# Control_Sense_TOP_VAC.net
KiCad netlist of a schematic drawn in Altium Designer
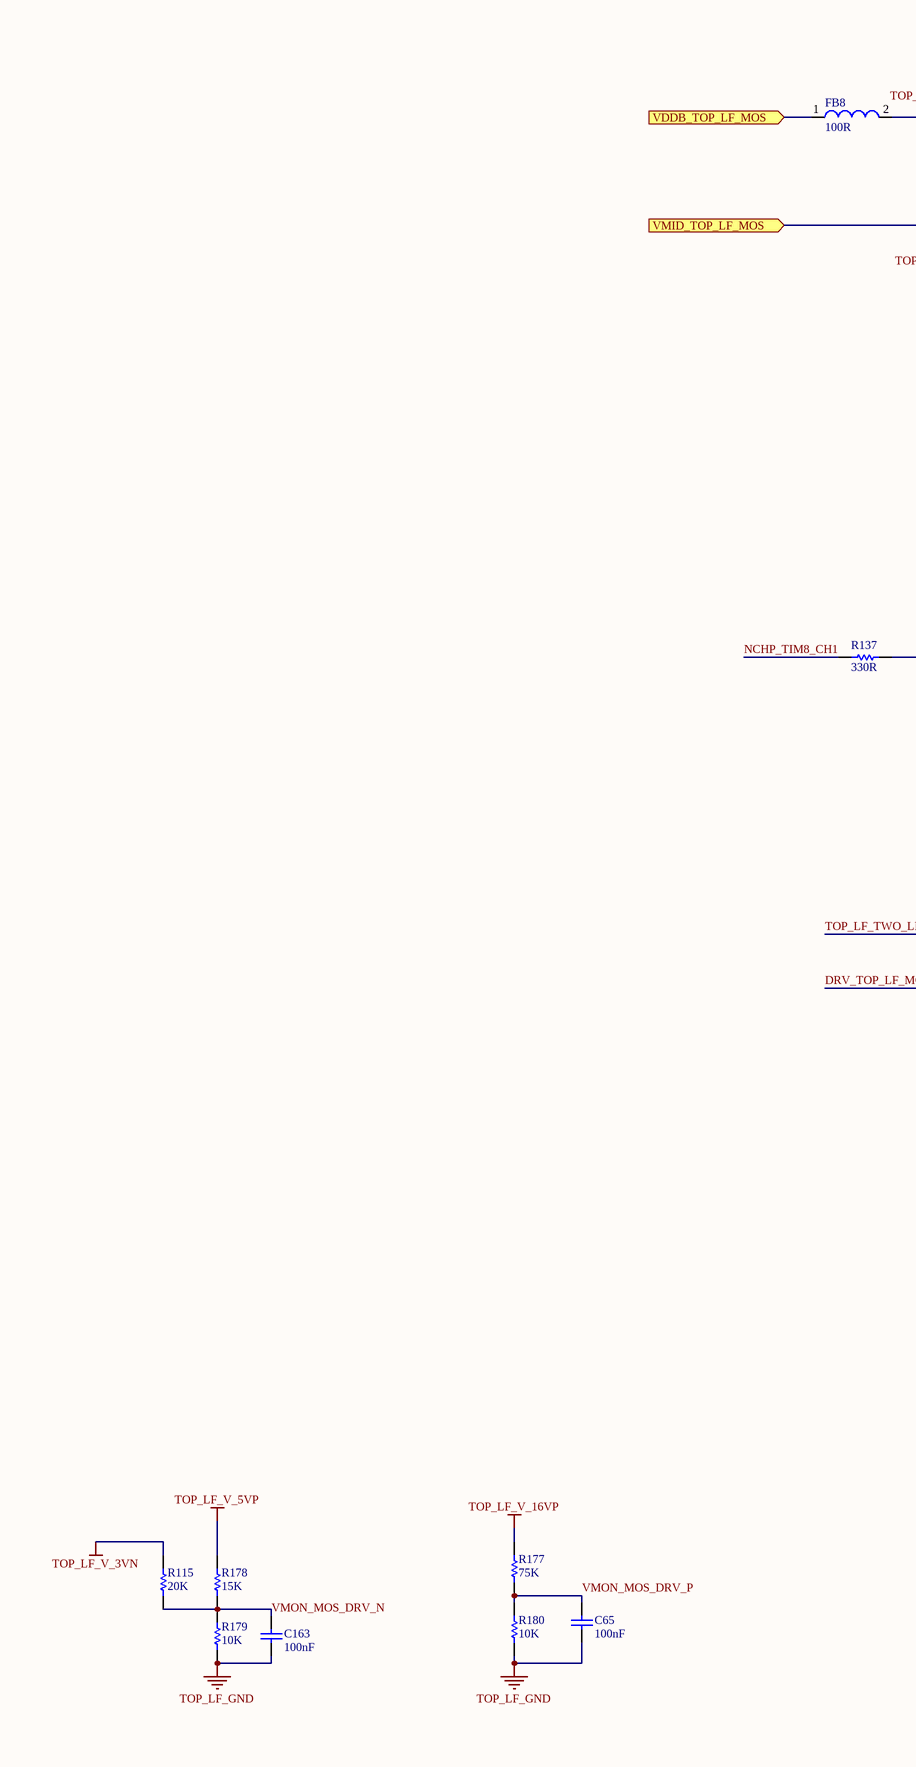
[diagram p0: Control_Sense_TOP_VAC.SchDoc, top left]
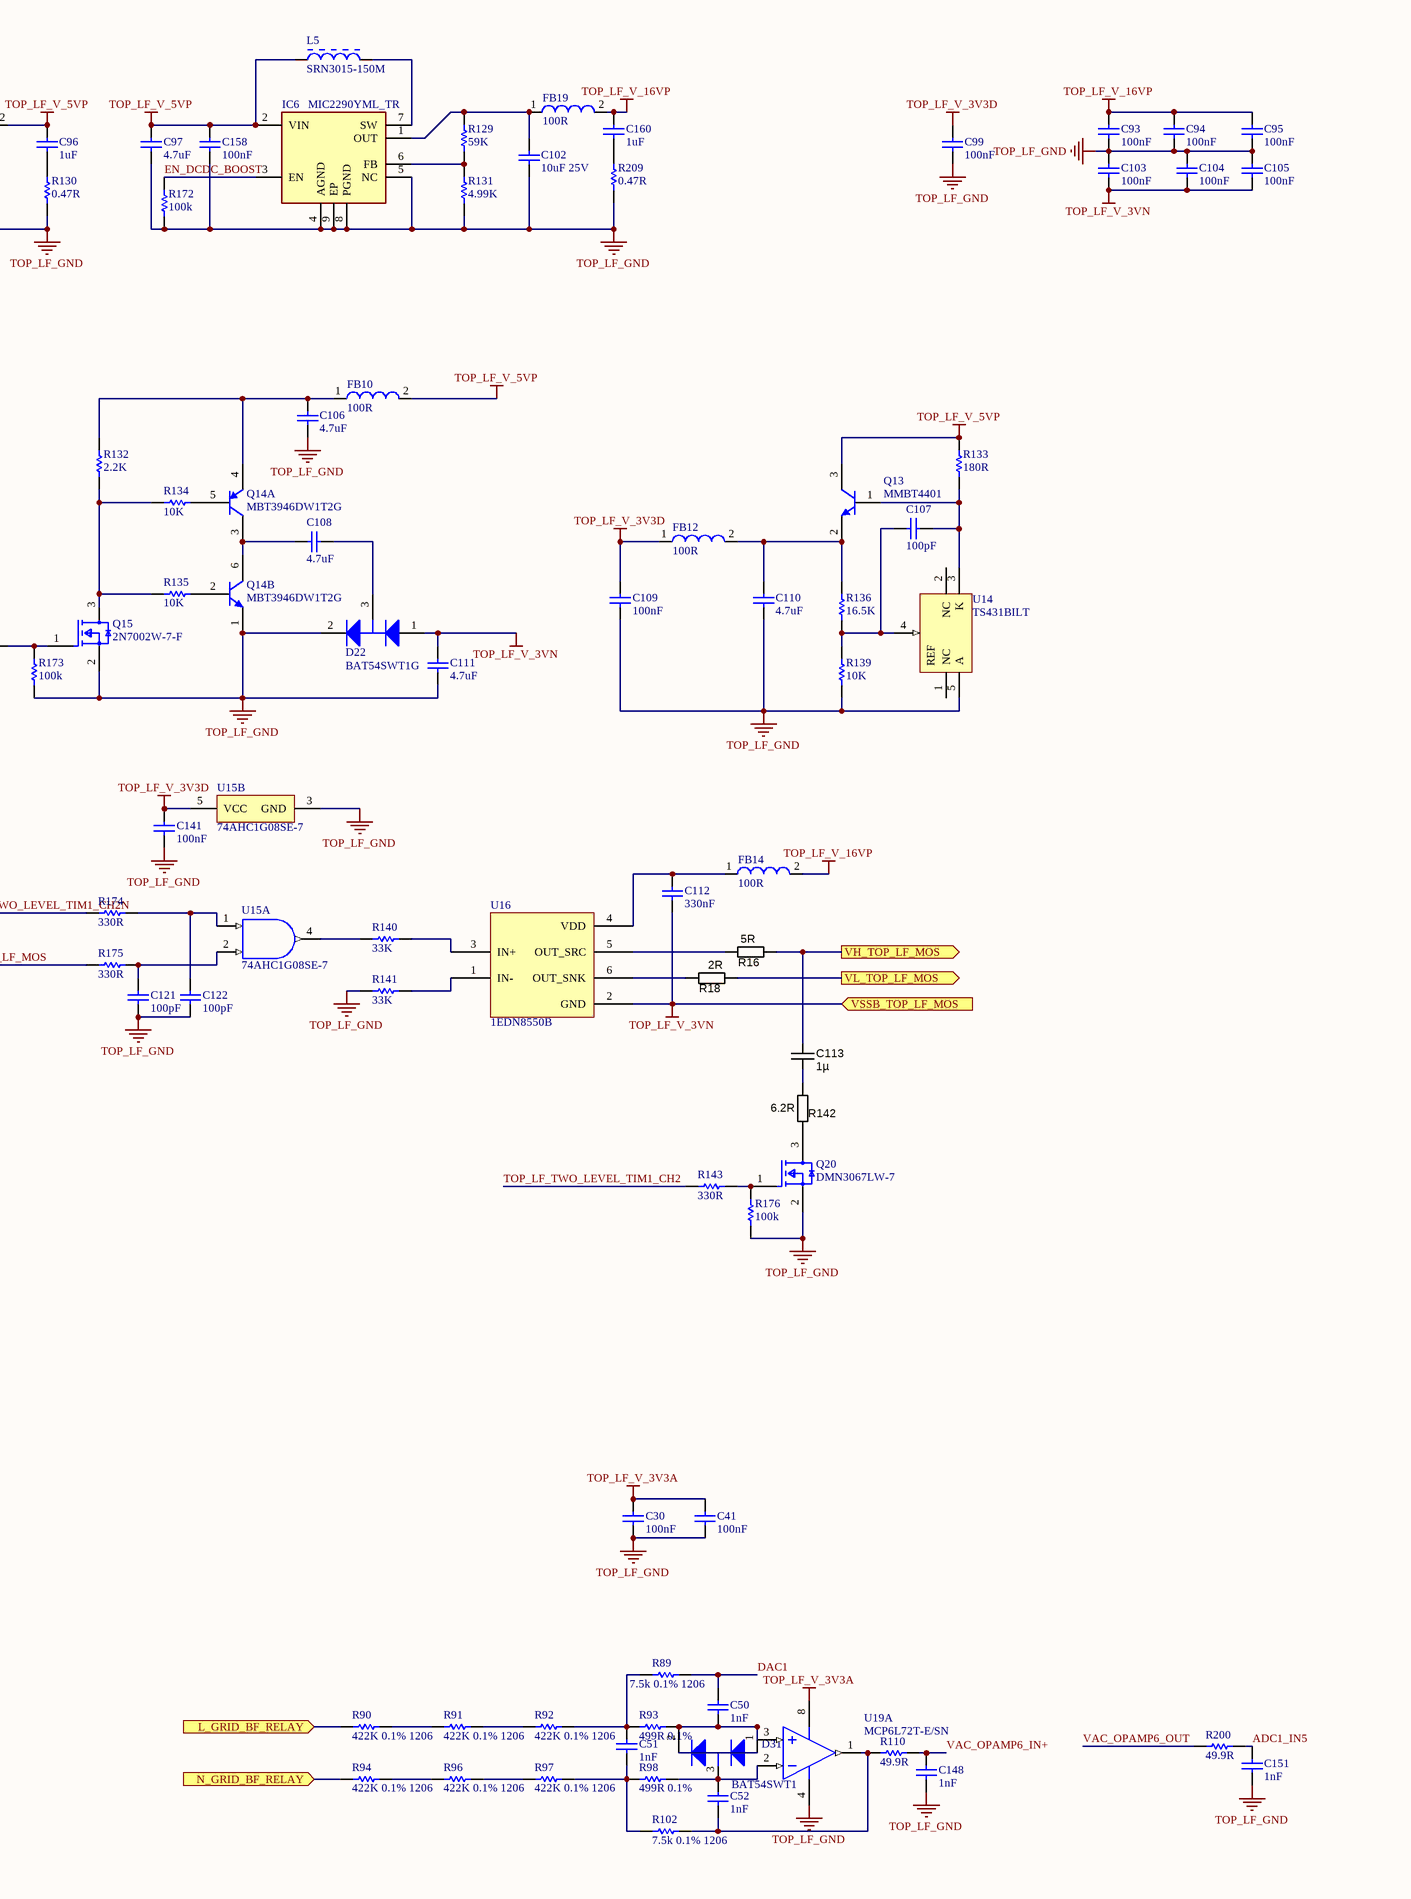
[diagram p1: Control_Sense_TOP_VAC.SchDoc, top right]
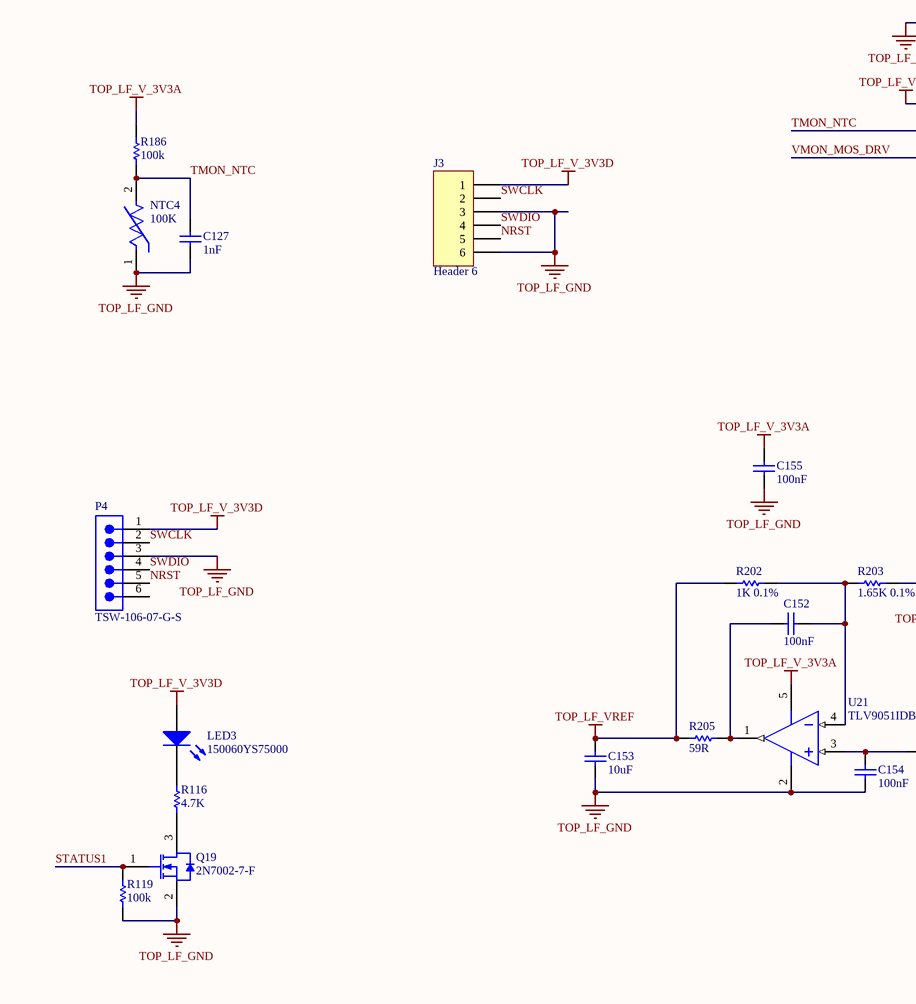
[diagram p2: Control_Sense_TOP_VAC.SchDoc, bottom left]
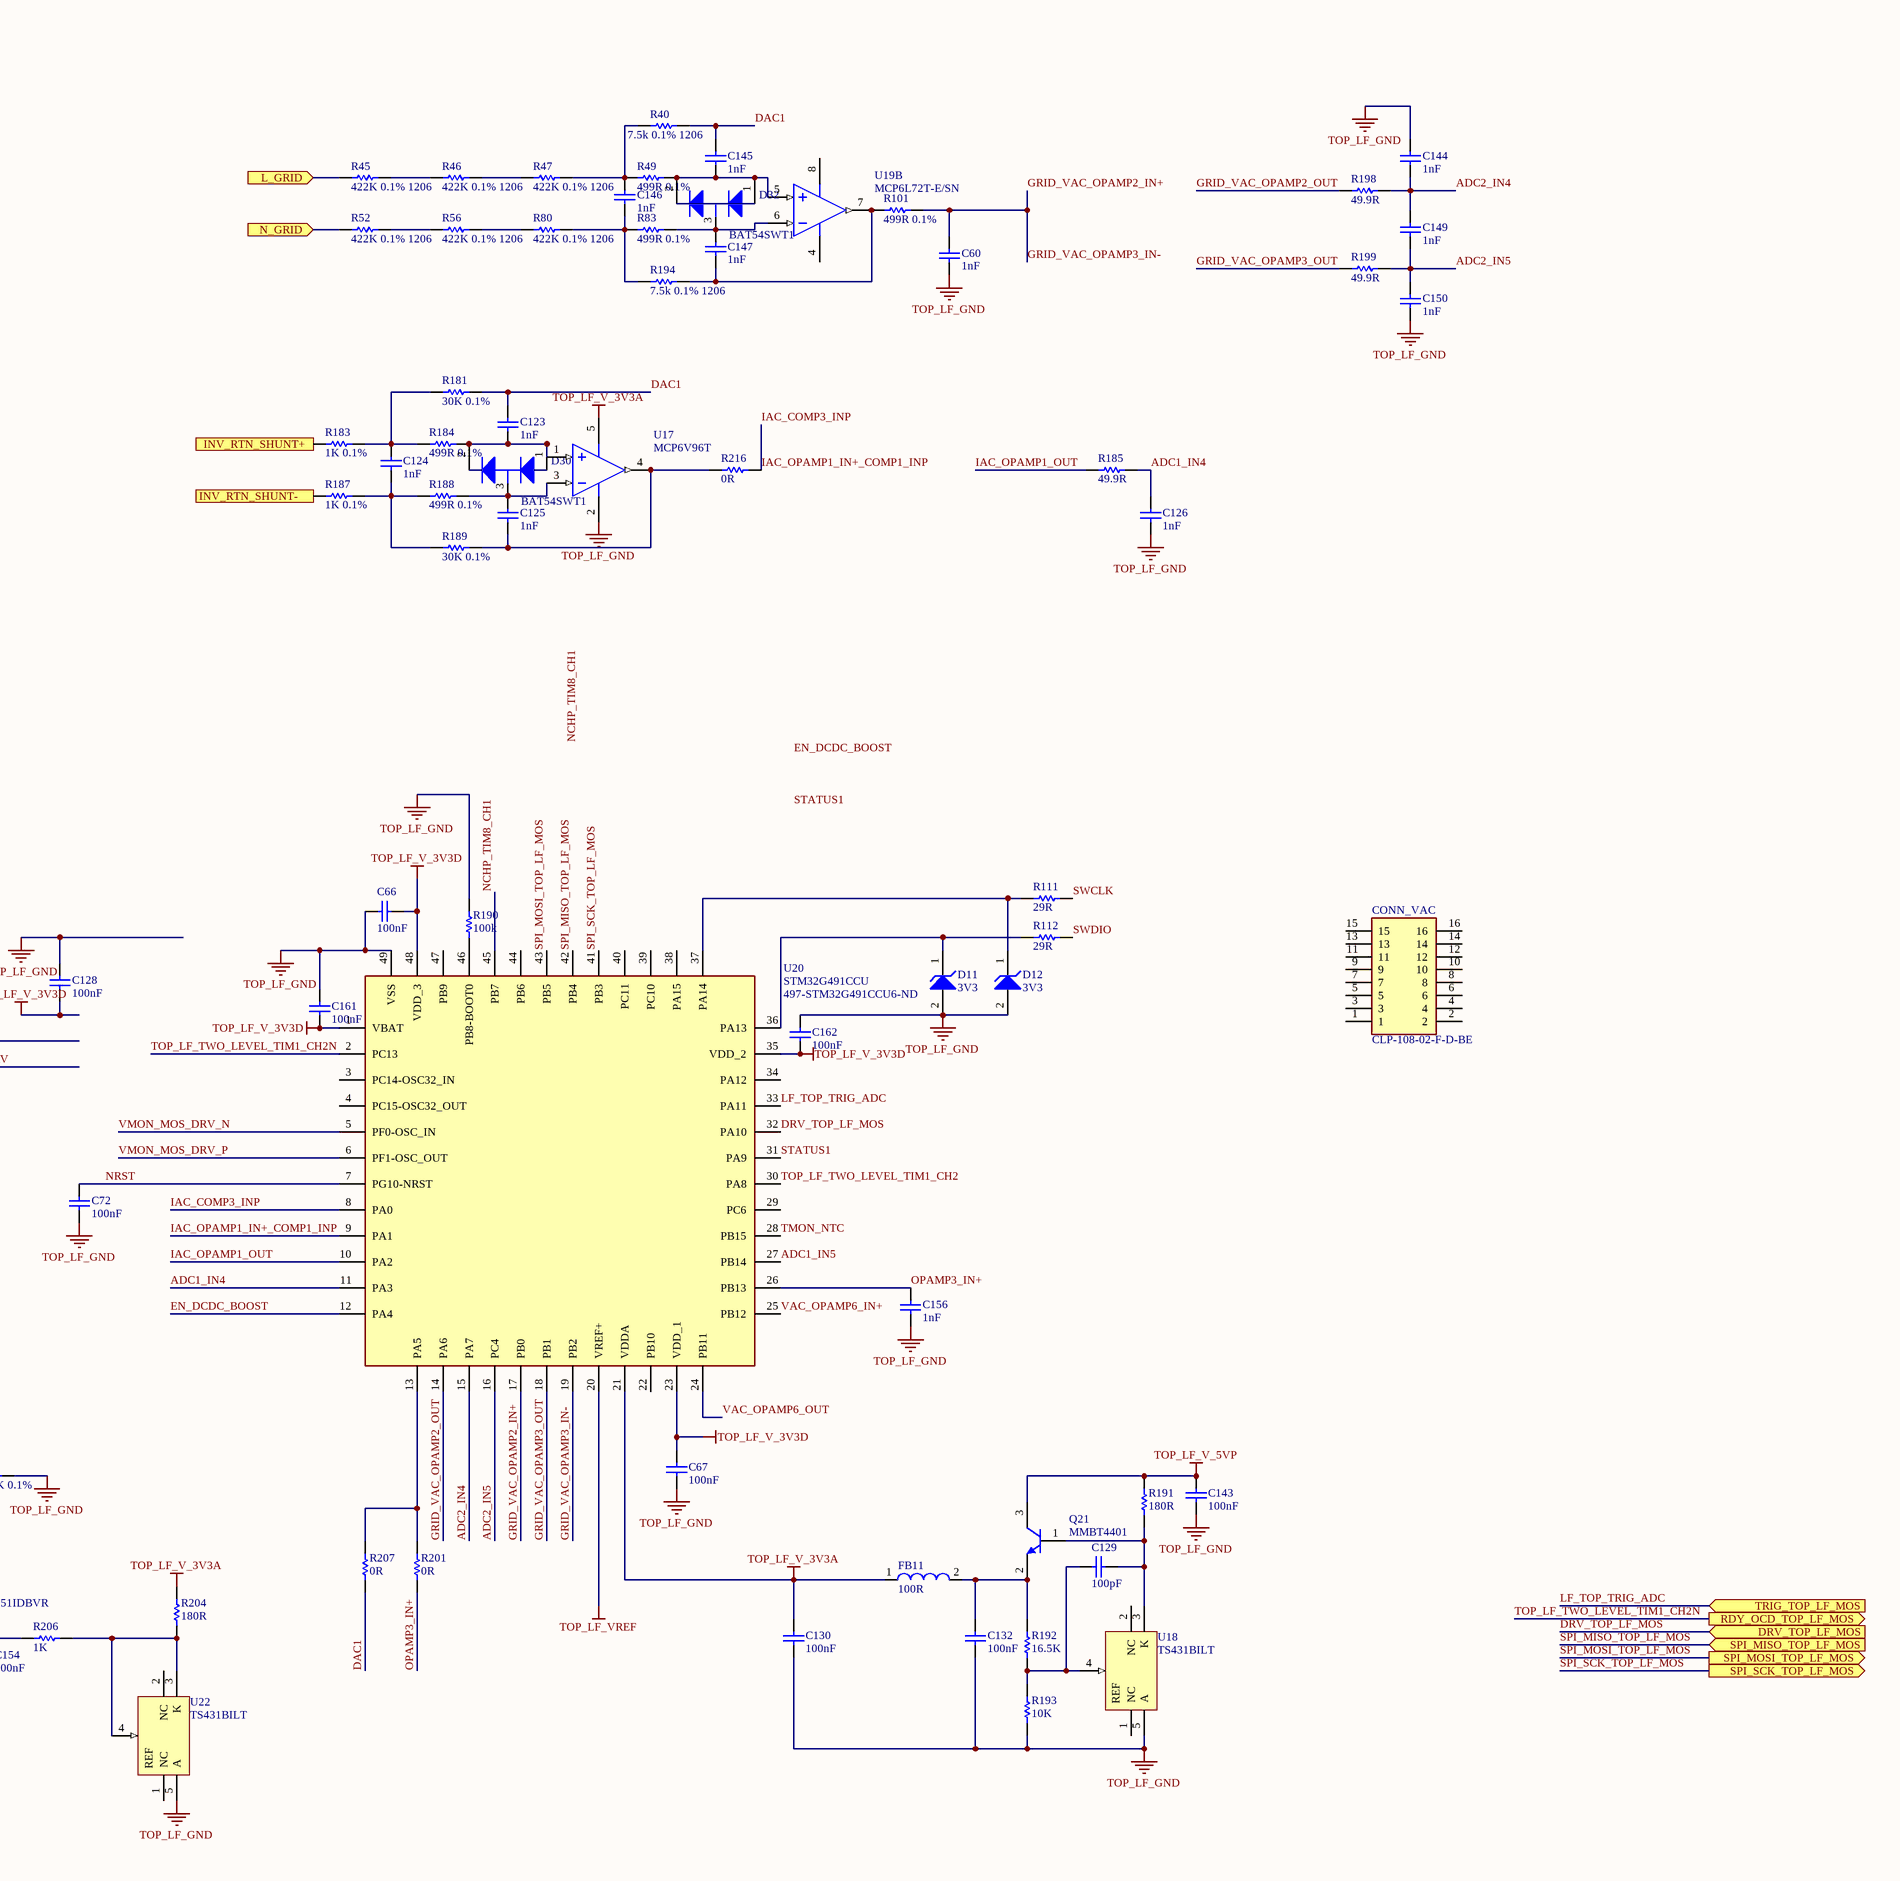
[diagram p3: Control_Sense_TOP_VAC.SchDoc, bottom right]

(export (version "E")
  (design (tool "Eeschema 10.0.6"))
  (components
    (comp (ref "C30")
      (value "100nF")
      (footprint "SAMS-C0603-2_N")
      (description "Cap Ceramic 0.1uF 50VDC X7R 10% SMD 0603 Paper T/R")
      (fields
        (field (name "MANUFACTURER") "Samsung Electro-Mechanics")
        (field (name "MANUFACTURER PART NUMBER") "CL10B104KB8NNNC")
      )
      (libsource (lib "Altium Content Vault") (part "CAP-NP-2"))
    )
    (comp (ref "C41")
      (value "100nF")
      (footprint "SAMS-C0603-2_N")
      (description "Cap Ceramic 0.1uF 50VDC X7R 10% SMD 0603 Paper T/R")
      (fields
        (field (name "MANUFACTURER") "Samsung Electro-Mechanics")
        (field (name "MANUFACTURER PART NUMBER") "CL10B104KB8NNNC")
      )
      (libsource (lib "Altium Content Vault") (part "CAP-NP-2"))
    )
    (comp (ref "C50")
      (value "1nF")
      (footprint "CAPC1608X90X35NL15T15")
      (fields
        (field (name "MANUFACTURER") "AVX Interconnect / Elco")
        (field (name "PART NUMBER") "06035A151JAT2A.")
        (field (name "MANUFACTURER PART NUMBER") "06035A151JAT2A")
      )
      (libsource (lib "Altium Content Vault") (part "CAP"))
    )
    (comp (ref "C51")
      (value "1nF")
      (footprint "CAPC1608X90X35NL15T15")
      (fields
        (field (name "MANUFACTURER") "AVX Interconnect / Elco")
        (field (name "PART NUMBER") "06035A151JAT2A.")
        (field (name "MANUFACTURER PART NUMBER") "06035A151JAT2A")
      )
      (libsource (lib "Altium Content Vault") (part "CAP"))
    )
    (comp (ref "C52")
      (value "1nF")
      (footprint "CAPC1608X90X35NL15T15")
      (fields
        (field (name "MANUFACTURER") "AVX Interconnect / Elco")
        (field (name "PART NUMBER") "06035A151JAT2A.")
        (field (name "MANUFACTURER PART NUMBER") "06035A151JAT2A")
      )
      (libsource (lib "Altium Content Vault") (part "CAP"))
    )
    (comp (ref "C60")
      (value "1nF")
      (footprint "CAPC1608X90X35LL15T15")
      (fields
        (field (name "MANUFACTURER") "AVX Interconnect / Elco")
        (field (name "PART NUMBER") "06035A151JAT2A.")
        (field (name "MANUFACTURER PART NUMBER") "06035A151JAT2A")
      )
      (libsource (lib "Altium Content Vault") (part "CAP"))
    )
    (comp (ref "C65")
      (value "100nF")
      (footprint "CAPC1005X56X25NL10T15")
      (fields
        (field (name "MANUFACTURER") "AVX Interconnect / Elco")
        (field (name "PART NUMBER") "04026D104KAT2A")
        (field (name "TOLERANCE") "10%")
      )
      (libsource (lib "Altium Content Vault") (part "CAP"))
    )
    (comp (ref "C66")
      (value "100nF")
      (footprint "SAMS-C0603-2_L")
      (description "Cap Ceramic 0.1uF 50VDC X7R 10% SMD 0603 Paper T/R")
      (fields
        (field (name "MANUFACTURER") "Samsung Electro-Mechanics")
        (field (name "MANUFACTURER PART NUMBER") "CL10B104KB8NNNC")
      )
      (libsource (lib "Altium Content Vault") (part "CAP-NP-2"))
    )
    (comp (ref "C67")
      (value "100nF")
      (footprint "SAMS-C0603-2_L")
      (description "Cap Ceramic 0.1uF 50VDC X7R 10% SMD 0603 Paper T/R")
      (fields
        (field (name "MANUFACTURER") "Samsung Electro-Mechanics")
        (field (name "MANUFACTURER PART NUMBER") "CL10B104KB8NNNC")
      )
      (libsource (lib "Altium Content Vault") (part "CAP-NP-2"))
    )
    (comp (ref "C72")
      (value "100nF")
      (footprint "CAPC1005X56X25NL10T15")
      (fields
        (field (name "MANUFACTURER") "AVX Interconnect / Elco")
        (field (name "PART NUMBER") "04026D104KAT2A")
        (field (name "TOLERANCE") "10%")
      )
      (libsource (lib "Altium Content Vault") (part "CAP"))
    )
    (comp (ref "C93")
      (value "100nF")
      (footprint "CAPC1608X90X35NL15T15")
      (fields
        (field (name "MANUFACTURER") "AVX Interconnect / Elco")
        (field (name "PART NUMBER") "06035A151JAT2A.")
        (field (name "MANUFACTURER PART NUMBER") "06035A151JAT2A")
      )
      (libsource (lib "Altium Content Vault") (part "CAP"))
    )
    (comp (ref "C94")
      (value "100nF")
      (footprint "CAPC1608X90X35NL15T15")
      (fields
        (field (name "MANUFACTURER") "AVX Interconnect / Elco")
        (field (name "PART NUMBER") "06035A151JAT2A.")
        (field (name "MANUFACTURER PART NUMBER") "06035A151JAT2A")
      )
      (libsource (lib "Altium Content Vault") (part "CAP"))
    )
    (comp (ref "C95")
      (value "100nF")
      (footprint "CAPC1608X90X35NL15T15")
      (fields
        (field (name "MANUFACTURER") "AVX Interconnect / Elco")
        (field (name "PART NUMBER") "06035A151JAT2A.")
        (field (name "MANUFACTURER PART NUMBER") "06035A151JAT2A")
      )
      (libsource (lib "Altium Content Vault") (part "CAP"))
    )
    (comp (ref "C96")
      (value "1uF")
      (footprint "CAPC2013X140X50LL20T25")
      (description "SMD Multilayer Ceramic Capacitor, 1 µF, 25 V, 0805 [2012 Metric], ± 10%, X7R")
      (fields (field (name "PART NUMBER") "C0805C105K3RACTU") (field (name "MANUFACTURER") "Kemet"))
      (libsource (lib "Altium Content Vault") (part "CAP"))
    )
    (comp (ref "C97")
      (value "4.7uF")
      (footprint "CAPC2013X145X20NL20")
      (description "Chip Capacitor, 4.7 uF, +/- 10%, 25 V, -55 to 125 degC, 0805 (2012 Metric), RoHS, Tape and Reel")
      (fields (field (name "MANUFACTURER") "TDK") (field (name "TOLERANCE") "±10%"))
      (libsource (lib "Altium Content Vault") (part "CAP-NP-2"))
    )
    (comp (ref "C99")
      (value "100nF")
      (footprint "CAPC1608X90X35ML15T15")
      (fields
        (field (name "MANUFACTURER") "AVX Interconnect / Elco")
        (field (name "PART NUMBER") "06035A151JAT2A.")
        (field (name "MANUFACTURER PART NUMBER") "06035A151JAT2A")
      )
      (libsource (lib "Altium Content Vault") (part "CAP"))
    )
    (comp (ref "C102")
      (value "10uF 25V")
      (footprint "CAPC3216X229X50LL20T25")
      (description "Chip Capacitor, 10 uF, +/- 10%, 25 V, -55 to 85 degC, 1206 (3216 Metric), RoHS, Tape and Reel")
      (fields (field (name "MANUFACTURER") "AVX"))
      (libsource (lib "Altium Content Vault") (part "CAP-NP-2"))
    )
    (comp (ref "C103")
      (value "100nF")
      (footprint "CAPC1608X90X35NL15T15")
      (fields
        (field (name "MANUFACTURER") "AVX Interconnect / Elco")
        (field (name "PART NUMBER") "06035A151JAT2A.")
        (field (name "MANUFACTURER PART NUMBER") "06035A151JAT2A")
      )
      (libsource (lib "Altium Content Vault") (part "CAP"))
    )
    (comp (ref "C104")
      (value "100nF")
      (footprint "CAPC1608X90X35NL15T15")
      (fields
        (field (name "MANUFACTURER") "AVX Interconnect / Elco")
        (field (name "PART NUMBER") "06035A151JAT2A.")
        (field (name "MANUFACTURER PART NUMBER") "06035A151JAT2A")
      )
      (libsource (lib "Altium Content Vault") (part "CAP"))
    )
    (comp (ref "C105")
      (value "100nF")
      (footprint "CAPC1608X90X35NL15T15")
      (fields
        (field (name "MANUFACTURER") "AVX Interconnect / Elco")
        (field (name "PART NUMBER") "06035A151JAT2A.")
        (field (name "MANUFACTURER PART NUMBER") "06035A151JAT2A")
      )
      (libsource (lib "Altium Content Vault") (part "CAP"))
    )
    (comp (ref "C106")
      (value "4.7uF")
      (footprint "SAMS-C0603-2_L")
      (description "Cap Ceramic 0.1uF 50VDC X7R 10% SMD 0603 Paper T/R")
      (fields
        (field (name "MANUFACTURER") "Samsung Electro-Mechanics")
        (field (name "MANUFACTURER PART NUMBER") "CL10B104KB8NNNC")
      )
      (libsource (lib "Altium Content Vault") (part "CAP-NP-2"))
    )
    (comp (ref "C107")
      (value "100pF")
      (footprint "CAPC1608X90X35NL10T15")
      (description "0603 100pF 50V ±5 % Tolerance C0G SMT Multilayer Ceramic Capacitor")
      (fields (field (name "PART NUMBER") "GRM1885C1H101JA01D") (field (name "MANUFACTURER") "Murata"))
      (libsource (lib "Altium Content Vault") (part "CAP"))
    )
    (comp (ref "C108")
      (value "4.7uF")
      (footprint "SAMS-C0603-2_L")
      (description "Cap Ceramic 0.1uF 50VDC X7R 10% SMD 0603 Paper T/R")
      (fields
        (field (name "MANUFACTURER") "Samsung Electro-Mechanics")
        (field (name "MANUFACTURER PART NUMBER") "CL10B104KB8NNNC")
      )
      (libsource (lib "Altium Content Vault") (part "CAP-NP-2"))
    )
    (comp (ref "C109")
      (value "100nF")
      (footprint "SAMS-C0603-2_N")
      (description "Cap Ceramic 0.1uF 50VDC X7R 10% SMD 0603 Paper T/R")
      (fields
        (field (name "MANUFACTURER") "Samsung Electro-Mechanics")
        (field (name "MANUFACTURER PART NUMBER") "CL10B104KB8NNNC")
      )
      (libsource (lib "Altium Content Vault") (part "CAP-NP-2"))
    )
    (comp (ref "C110")
      (value "4.7uF")
      (footprint "CAPC1608X90X35LL15T15")
      (description "Cap Ceramic 4.7uF 6.3VDC X5R 10% SMD 0603 Paper T/R")
      (fields
        (field (name "PART NUMBER") "06036D475KAT2A")
        (field (name "MANUFACTURER") "AVX Interconnect / Elco")
      )
      (libsource (lib "Altium Content Vault") (part "CAP"))
    )
    (comp (ref "C111")
      (value "4.7uF")
      (footprint "SAMS-C0603-2_L")
      (description "Cap Ceramic 4.7uF 6.3VDC X5R 10% SMD 0603 Paper T/R")
      (fields
        (field (name "MANUFACTURER") "Samsung Electro-Mechanics")
        (field (name "MANUFACTURER PART NUMBER") "CL10B104KB8NNNC")
      )
      (libsource (lib "Altium Content Vault") (part "CAP-NP-2"))
    )
    (comp (ref "C112")
      (value "330nF")
      (footprint "CAPC2013X135X45NL10T25")
      (description "Chip Capacitor, 0.1 uF, +/- 10%, 50 V, -55 to 125 degC, 0805 (2012 Metric), RoHS, Tape and Reel")
      (fields (field (name "VOLTAGE") "50V") (field (name "TOLERANCE") "10%"))
      (libsource (lib "Altium Content Vault") (part "CAP-NP-2"))
    )
    (comp (ref "C113")
      (value "1µ")
      (footprint "CAPC2012X135N")
      (description "Capacitor SMD Cer 1uF 10% 16V X7R 0805")
      (fields (field (name "TOLERANCE") "±10%") (field (name "Comment") "approved sub OK"))
      (libsource (lib "PBL - Capacitors") (part "CAPC_1u_0805_X7R_16V_10%"))
    )
    (comp (ref "C121")
      (value "100pF")
      (footprint "CAPC1608X90X35NL10T15")
      (fields
        (field (name "PART NUMBER") "GRM1885C1H101JA01D")
        (field (name "MANUFACTURER") "Murata")
        (field (name "TOLERANCE") "5%")
      )
      (libsource (lib "Altium Content Vault") (part "CAP"))
    )
    (comp (ref "C122")
      (value "100pF")
      (footprint "CAPC1608X90X35NL10T15")
      (fields
        (field (name "PART NUMBER") "GRM1885C1H101JA01D")
        (field (name "MANUFACTURER") "Murata")
        (field (name "TOLERANCE") "5%")
      )
      (libsource (lib "Altium Content Vault") (part "CAP"))
    )
    (comp (ref "C123")
      (value "1nF")
      (footprint "CAPC1608X90X35NL15T15")
      (fields
        (field (name "MANUFACTURER") "AVX Interconnect / Elco")
        (field (name "PART NUMBER") "06035A151JAT2A.")
        (field (name "MANUFACTURER PART NUMBER") "06035A151JAT2A")
      )
      (libsource (lib "Altium Content Vault") (part "CAP"))
    )
    (comp (ref "C124")
      (value "1nF")
      (footprint "CAPC1608X90X35LL15T15")
      (fields
        (field (name "MANUFACTURER") "AVX Interconnect / Elco")
        (field (name "PART NUMBER") "06035A151JAT2A.")
        (field (name "MANUFACTURER PART NUMBER") "06035A151JAT2A")
      )
      (libsource (lib "Altium Content Vault") (part "CAP"))
    )
    (comp (ref "C125")
      (value "1nF")
      (footprint "CAPC1608X90X35NL15T15")
      (fields
        (field (name "MANUFACTURER") "AVX Interconnect / Elco")
        (field (name "PART NUMBER") "06035A151JAT2A.")
        (field (name "MANUFACTURER PART NUMBER") "06035A151JAT2A")
      )
      (libsource (lib "Altium Content Vault") (part "CAP"))
    )
    (comp (ref "C126")
      (value "1nF")
      (footprint "CAPC1005X56X25NL10T15")
      (fields
        (field (name "MANUFACTURER") "AVX Interconnect / Elco")
        (field (name "PART NUMBER") "04025C102MAT2A")
        (field (name "TOLERANCE") "20%")
      )
      (libsource (lib "Altium Content Vault") (part "CAP"))
    )
    (comp (ref "C127")
      (value "1nF")
      (footprint "CAPC1005X56X25NL10T15")
      (fields
        (field (name "MANUFACTURER") "AVX Interconnect / Elco")
        (field (name "PART NUMBER") "04025C102MAT2A")
        (field (name "TOLERANCE") "20%")
      )
      (libsource (lib "Altium Content Vault") (part "CAP"))
    )
    (comp (ref "C128")
      (value "100nF")
      (footprint "SAMS-C0603-2_N")
      (description "Cap Ceramic 0.1uF 50VDC X7R 10% SMD 0603 Paper T/R")
      (fields
        (field (name "MANUFACTURER") "Samsung Electro-Mechanics")
        (field (name "MANUFACTURER PART NUMBER") "CL10B104KB8NNNC")
      )
      (libsource (lib "Altium Content Vault") (part "CAP-NP-2"))
    )
    (comp (ref "C129")
      (value "100pF")
      (footprint "CAPC1608X90X35NL10T15")
      (description "0603 100pF 50V ±5 % Tolerance C0G SMT Multilayer Ceramic Capacitor")
      (fields (field (name "PART NUMBER") "GRM1885C1H101JA01D") (field (name "MANUFACTURER") "Murata"))
      (libsource (lib "Altium Content Vault") (part "CAP"))
    )
    (comp (ref "C130")
      (value "100nF")
      (footprint "SAMS-C0603-2_L")
      (description "Cap Ceramic 0.1uF 50VDC X7R 10% SMD 0603 Paper T/R")
      (fields
        (field (name "MANUFACTURER") "Samsung Electro-Mechanics")
        (field (name "MANUFACTURER PART NUMBER") "CL10B104KB8NNNC")
      )
      (libsource (lib "Altium Content Vault") (part "CAP-NP-2"))
    )
    (comp (ref "C132")
      (value "100nF")
      (footprint "SAMS-C0603-2_N")
      (description "Cap Ceramic 0.1uF 50VDC X7R 10% SMD 0603 Paper T/R")
      (fields
        (field (name "MANUFACTURER") "Samsung Electro-Mechanics")
        (field (name "MANUFACTURER PART NUMBER") "CL10B104KB8NNNC")
      )
      (libsource (lib "Altium Content Vault") (part "CAP-NP-2"))
    )
    (comp (ref "C141")
      (value "100nF")
      (footprint "CAPC1608X90X35LL15T15")
      (fields
        (field (name "MANUFACTURER") "AVX Interconnect / Elco")
        (field (name "PART NUMBER") "06035A151JAT2A.")
        (field (name "MANUFACTURER PART NUMBER") "06035A151JAT2A")
      )
      (libsource (lib "Altium Content Vault") (part "CAP"))
    )
    (comp (ref "C143")
      (value "100nF")
      (footprint "SAMS-C0603-2_N")
      (description "Cap Ceramic 0.1uF 50VDC X7R 10% SMD 0603 Paper T/R")
      (fields
        (field (name "MANUFACTURER") "Samsung Electro-Mechanics")
        (field (name "MANUFACTURER PART NUMBER") "CL10B104KB8NNNC")
      )
      (libsource (lib "Altium Content Vault") (part "CAP-NP-2"))
    )
    (comp (ref "C144")
      (value "1nF")
      (footprint "CAPC1005X56X25LL10T15")
      (fields
        (field (name "MANUFACTURER") "AVX Interconnect / Elco")
        (field (name "PART NUMBER") "04025C102MAT2A")
        (field (name "TOLERANCE") "20%")
      )
      (libsource (lib "Altium Content Vault") (part "CAP"))
    )
    (comp (ref "C145")
      (value "1nF")
      (footprint "CAPC1608X90X35NL15T15")
      (fields
        (field (name "MANUFACTURER") "AVX Interconnect / Elco")
        (field (name "PART NUMBER") "06035A151JAT2A.")
        (field (name "MANUFACTURER PART NUMBER") "06035A151JAT2A")
      )
      (libsource (lib "Altium Content Vault") (part "CAP"))
    )
    (comp (ref "C146")
      (value "1nF")
      (footprint "CAPC1608X90X35NL15T15")
      (fields
        (field (name "MANUFACTURER") "AVX Interconnect / Elco")
        (field (name "PART NUMBER") "06035A151JAT2A.")
        (field (name "MANUFACTURER PART NUMBER") "06035A151JAT2A")
      )
      (libsource (lib "Altium Content Vault") (part "CAP"))
    )
    (comp (ref "C147")
      (value "1nF")
      (footprint "CAPC1608X90X35NL15T15")
      (fields
        (field (name "MANUFACTURER") "AVX Interconnect / Elco")
        (field (name "PART NUMBER") "06035A151JAT2A.")
        (field (name "MANUFACTURER PART NUMBER") "06035A151JAT2A")
      )
      (libsource (lib "Altium Content Vault") (part "CAP"))
    )
    (comp (ref "C148")
      (value "1nF")
      (footprint "CAPC1005X56X25NL10T15")
      (fields
        (field (name "MANUFACTURER") "AVX Interconnect / Elco")
        (field (name "PART NUMBER") "04025C102MAT2A")
        (field (name "TOLERANCE") "20%")
      )
      (libsource (lib "Altium Content Vault") (part "CAP"))
    )
    (comp (ref "C149")
      (value "1nF")
      (footprint "CAPC1005X56X25LL10T15")
      (fields
        (field (name "MANUFACTURER") "AVX Interconnect / Elco")
        (field (name "PART NUMBER") "04025C102MAT2A")
        (field (name "TOLERANCE") "20%")
      )
      (libsource (lib "Altium Content Vault") (part "CAP"))
    )
    (comp (ref "C150")
      (value "1nF")
      (footprint "CAPC1005X56X25LL10T15")
      (fields
        (field (name "MANUFACTURER") "AVX Interconnect / Elco")
        (field (name "PART NUMBER") "04025C102MAT2A")
        (field (name "TOLERANCE") "20%")
      )
      (libsource (lib "Altium Content Vault") (part "CAP"))
    )
    (comp (ref "C151")
      (value "1nF")
      (footprint "CAPC1005X56X25NL10T15")
      (fields
        (field (name "MANUFACTURER") "AVX Interconnect / Elco")
        (field (name "PART NUMBER") "04025C102MAT2A")
        (field (name "TOLERANCE") "20%")
      )
      (libsource (lib "Altium Content Vault") (part "CAP"))
    )
    (comp (ref "C152")
      (value "100nF")
      (footprint "SAMS-C0603-2_L")
      (description "Cap Ceramic 0.1uF 50VDC X7R 10% SMD 0603 Paper T/R")
      (fields
        (field (name "MANUFACTURER") "Samsung Electro-Mechanics")
        (field (name "MANUFACTURER PART NUMBER") "CL10B104KB8NNNC")
      )
      (libsource (lib "Altium Content Vault") (part "CAP-NP-2"))
    )
    (comp (ref "C153")
      (value "10uF")
      (footprint "CAPC1608X90X35LL15T15")
      (fields
        (field (name "MANUFACTURER") "AVX Interconnect / Elco")
        (field (name "PART NUMBER") "06036D106MAT2A")
      )
      (libsource (lib "Altium Content Vault") (part "CAP"))
    )
    (comp (ref "C154")
      (value "100nF")
      (footprint "SAMS-C0603-2_L")
      (description "Cap Ceramic 0.1uF 50VDC X7R 10% SMD 0603 Paper T/R")
      (fields
        (field (name "MANUFACTURER") "Samsung Electro-Mechanics")
        (field (name "MANUFACTURER PART NUMBER") "CL10B104KB8NNNC")
      )
      (libsource (lib "Altium Content Vault") (part "CAP-NP-2"))
    )
    (comp (ref "C155")
      (value "100nF")
      (footprint "SAMS-C0603-2_L")
      (description "Cap Ceramic 0.1uF 50VDC X7R 10% SMD 0603 Paper T/R")
      (fields
        (field (name "MANUFACTURER") "Samsung Electro-Mechanics")
        (field (name "MANUFACTURER PART NUMBER") "CL10B104KB8NNNC")
      )
      (libsource (lib "Altium Content Vault") (part "CAP-NP-2"))
    )
    (comp (ref "C156")
      (value "1nF")
      (footprint "CAPC1005X56X25LL10T15")
      (fields
        (field (name "MANUFACTURER") "AVX Interconnect / Elco")
        (field (name "PART NUMBER") "04025C102MAT2A")
        (field (name "TOLERANCE") "20%")
      )
      (libsource (lib "Altium Content Vault") (part "CAP"))
    )
    (comp (ref "C158")
      (value "100nF")
      (footprint "CAPC1608X90X35LL15T15")
      (fields
        (field (name "MANUFACTURER") "AVX Interconnect / Elco")
        (field (name "PART NUMBER") "06035A151JAT2A.")
        (field (name "MANUFACTURER PART NUMBER") "06035A151JAT2A")
      )
      (libsource (lib "Altium Content Vault") (part "CAP"))
    )
    (comp (ref "C160")
      (value "1uF")
      (footprint "CAPC2013X140X50LL20T25")
      (description "SMD Multilayer Ceramic Capacitor, 1 µF, 25 V, 0805 [2012 Metric], ± 10%, X7R")
      (fields (field (name "PART NUMBER") "C0805C105K3RACTU") (field (name "MANUFACTURER") "Kemet"))
      (libsource (lib "Altium Content Vault") (part "CAP"))
    )
    (comp (ref "C161")
      (value "100nF")
      (footprint "SAMS-C0603-2_L")
      (description "Cap Ceramic 0.1uF 50VDC X7R 10% SMD 0603 Paper T/R")
      (fields
        (field (name "MANUFACTURER") "Samsung Electro-Mechanics")
        (field (name "MANUFACTURER PART NUMBER") "CL10B104KB8NNNC")
      )
      (libsource (lib "Altium Content Vault") (part "CAP-NP-2"))
    )
    (comp (ref "C162")
      (value "100nF")
      (footprint "SAMS-C0603-2_L")
      (description "Cap Ceramic 0.1uF 50VDC X7R 10% SMD 0603 Paper T/R")
      (fields
        (field (name "MANUFACTURER") "Samsung Electro-Mechanics")
        (field (name "MANUFACTURER PART NUMBER") "CL10B104KB8NNNC")
      )
      (libsource (lib "Altium Content Vault") (part "CAP-NP-2"))
    )
    (comp (ref "C163")
      (value "100nF")
      (footprint "CAPC1005X56X25NL10T15")
      (fields
        (field (name "MANUFACTURER") "AVX Interconnect / Elco")
        (field (name "PART NUMBER") "04026D104KAT2A")
        (field (name "TOLERANCE") "10%")
      )
      (libsource (lib "Altium Content Vault") (part "CAP"))
    )
    (comp (ref "CONN_VAC")
      (value "CLP-108-02-F-D-BE")
      (footprint "SamacSys:CLP-108-02-XXX-D-BE")
      (description "Connector")
      (fields (field (name "MOUSER PART NUMBER") "200-CLP10802FDBE"))
      (libsource (lib "*") (part "CLP-108-02-F-D-BE"))
    )
    (comp (ref "D11")
      (value "3V3")
      (footprint "ONSC-SOD-523-2-502-01_V")
      (fields (field (name "MANUFACTURER") "On Semiconductor") (field (name "PARTNUMBER") "ESD5Z3.3T1G"))
      (libsource (lib "Altium Content Vault") (part "ONSC-K1A2-2"))
    )
    (comp (ref "D12")
      (value "3V3")
      (footprint "ONSC-SOD-523-2-502-01_V")
      (fields (field (name "MANUFACTURER") "On Semiconductor") (field (name "PARTNUMBER") "ESD5Z3.3T1G"))
      (libsource (lib "Altium Content Vault") (part "ONSC-K1A2-2"))
    )
    (comp (ref "D22")
      (value "BAT54SWT1G")
      (footprint "ONSC-SOT-323-3-419-04_V")
      (description "Dual Series Schottky Barrier Diodes, 3-Pin SOT-323, Pb-Free, Tape and Reel")
      (fields (field (name "MANUFACTURER") "On Semiconductor"))
      (libsource (lib "") (part "ONSC-D-A1K2C3-3_1"))
    )
    (comp (ref "D30")
      (value "BAT54SWT1")
      (footprint "ONSC-SOT-323-3-419-04_V")
      (description "Dual Series Schottky Barrier Diodes, 3-Pin SOT-323, Tape and Reel")
      (fields (field (name "MANUFACTURER") "On Semiconductor"))
      (libsource (lib "Altium Content Vault") (part "ONSC-D-A1K2C3-3"))
    )
    (comp (ref "D31")
      (value "BAT54SWT1")
      (footprint "ONSC-SOT-323-3-419-04_V")
      (description "Dual Series Schottky Barrier Diodes, 3-Pin SOT-323, Tape and Reel")
      (fields (field (name "MANUFACTURER") "On Semiconductor"))
      (libsource (lib "Altium Content Vault") (part "ONSC-D-A1K2C3-3"))
    )
    (comp (ref "D32")
      (value "BAT54SWT1")
      (footprint "ONSC-SOT-323-3-419-04_V")
      (description "Dual Series Schottky Barrier Diodes, 3-Pin SOT-323, Tape and Reel")
      (fields (field (name "MANUFACTURER") "On Semiconductor"))
      (libsource (lib "Altium Content Vault") (part "ONSC-D-A1K2C3-3"))
    )
    (comp (ref "FB8")
      (value "100R")
      (footprint "SMD-0603")
      (description "SMD EMI Suppression Ferrite Bead WE-CBF, Z = 1500 Ohm")
      (libsource (lib "Altium Content Vault") (part "PAS-IND-INDUCTOR-2"))
    )
    (comp (ref "FB10")
      (value "100R")
      (footprint "SMD-0603")
      (description "SMD EMI Suppression Ferrite Bead WE-CBF, Z = 1500 Ohm")
      (libsource (lib "Altium Content Vault") (part "PAS-IND-INDUCTOR-2"))
    )
    (comp (ref "FB11")
      (value "100R")
      (footprint "SMD-0603")
      (description "SMD EMI Suppression Ferrite Bead WE-CBF, Z = 1500 Ohm")
      (libsource (lib "Altium Content Vault") (part "PAS-IND-INDUCTOR-2"))
    )
    (comp (ref "FB12")
      (value "100R")
      (footprint "SMD-0603")
      (description "SMD EMI Suppression Ferrite Bead WE-CBF, Z = 1500 Ohm")
      (libsource (lib "Altium Content Vault") (part "PAS-IND-INDUCTOR-2"))
    )
    (comp (ref "FB14")
      (value "100R")
      (footprint "SMD-0603")
      (description "SMD EMI Suppression Ferrite Bead WE-CBF, Z = 1500 Ohm")
      (libsource (lib "Altium Content Vault") (part "PAS-IND-INDUCTOR-2"))
    )
    (comp (ref "FB19")
      (value "100R")
      (footprint "SMD-0603")
      (description "SMD EMI Suppression Ferrite Bead WE-CBF, Z = 1500 Ohm")
      (libsource (lib "Altium Content Vault") (part "PAS-IND-INDUCTOR-2"))
    )
    (comp (ref "IC6")
      (value "MIC2290YML_TR")
      (footprint "SamacSys:SON50P200X200X95-9N-D")
      (description "Integrated Circuit")
      (fields (field (name "MANUFACTURER_PART_NUMBER") "MIC2290YML TR"))
      (libsource (lib "*") (part "MIC2290YML_TR"))
    )
    (comp (ref "J3")
      (value "Header 6")
      (footprint "HDR1X6")
      (description "Header, 6-Pin")
      (fields (field (name "PUBLISHER") "Altium Limited"))
      (libsource (lib "Miscellaneous Connectors") (part "Header 6"))
    )
    (comp (ref "L5")
      (value "SRN3015-150M")
      (footprint "BOUR-SRN3015-2_V")
      (fields (field (name "MANUFACTURER") "Bourns") (field (name "TOLERANCE") "20%"))
      (libsource (lib "Altium Content Vault") (part "BOUR-IND-2A"))
    )
    (comp (ref "LED3")
      (value "150060YS75000")
      (footprint "0603_A")
      (description "SMD mono-color Chip LED, WL-SMCW, Yellow")
      (fields (field (name "MANUFACTURER") "Wuerth Elektronik"))
      (libsource (lib "Altium Content Vault") (part "WE-LED_K1A2-2"))
    )
    (comp (ref "NTC4")
      (value "100K")
      (footprint "FP-NXR_151B030-MFG")
      (description "Thermistor NTC 10kΩ ±1% 2-Pin Radial Bulk")
      (fields (field (name "TOLERANCE") "1%"))
      (libsource (lib "Altium Content Vault") (part "3b148a6ebabc5fb4d708a66c052d352"))
    )
    (comp (ref "P4")
      (value "TSW-106-07-G-S")
      (footprint "SMTC-TSW-106-07-X-S")
      (description "0.025\" SQ Post Header, Through-hole, Vertical, -55 to 125 degC, 2.54 mm Pitch, 6-Pin, Male, RoHS")
      (fields (field (name "MANUFACTURER") "Samtec"))
      (libsource (lib "Altium Content Vault") (part "SMTC-TSW-106-X-X-S-X"))
    )
    (comp (ref "Q13")
      (value "MMBT4401")
      (footprint "FAIR-SOT23-3_V")
      (description "NPN General-Purpose Amplifier, 0.6 A, 40 V, -55 to 150 degC, 3-Pin SOT-23, RoHS, Tape and Reel")
      (fields (field (name "MANUFACTURER") "FairchildSemiconductor"))
      (libsource (lib "Altium Content Vault") (part "BJT-NPN-BEC-3"))
    )
    (comp (ref "Q14")
      (value "MBT3946DW1T2G")
      (footprint "ONSC-SC70-6-419B-02_W_V")
      (description "Complementary General Purpose Transistors, 6-Pin SC70, Pb-Free, Tape and Reel")
      (fields (field (name "MANUFACTURER") "On Semiconductor"))
      (libsource (lib "Altium Content Vault") (part "ONSC-NPN_PNP-6"))
    )
    (comp (ref "Q15")
      (value "2N7002W-7-F")
      (footprint "FP-SOT323-IPC_B")
      (description "MOSFET N-CH 60V 115MA SOT323")
      (libsource (lib "Altium Content Vault") (part "381a366367e4312d0f7d2747150cb42"))
    )
    (comp (ref "Q19")
      (value "2N7002-7-F")
      (footprint "DIOD-SOT23-3_V")
      (fields (field (name "MANUFACTURER") "DiodesIncorporated"))
      (libsource (lib "Altium Content Vault") (part "NEMOS-GSD-3"))
    )
    (comp (ref "Q20")
      (value "DMN3067LW-7")
      (footprint "FP-SOT323-IPC_C")
      (description "MOSFET N-CH 60V 115MA SOT323")
      (libsource (lib "Altium Content Vault") (part "381a366367e4312d0f7d2747150cb42"))
    )
    (comp (ref "Q21")
      (value "MMBT4401")
      (footprint "SOT23-3")
      (description "NPN General-Purpose Amplifier, 0.6 A, 40 V, -55 to 150 degC, 3-Pin SOT-23, RoHS, Tape and Reel")
      (fields (field (name "MANUFACTURER") "FairchildSemiconductor"))
      (libsource (lib "PBL - Transistors") (part "BJT-NPN-BEC-3"))
    )
    (comp (ref "R16")
      (value "5R")
      (footprint "RESC2012X70N")
      (description "Resistor, 0805 SMD, Empty footprint")
      (libsource (lib "PBL - Resistors") (part "RES_EMPTY_0805"))
    )
    (comp (ref "R18")
      (value "2R")
      (footprint "RESC2012X70N")
      (description "Resistor, 0805 SMD, Empty footprint")
      (libsource (lib "PBL - Resistors") (part "RES_EMPTY_0805"))
    )
    (comp (ref "R40")
      (value "7.5k 0.1% 1206")
      (footprint "RESC3216X50X50NL20T20")
      (fields (field (name "MANUFACTURER") "Susumu") (field (name "PART NUMBER") "RG3216P-1002-B-T5"))
      (libsource (lib "Altium Content Vault") (part "RES"))
    )
    (comp (ref "R45")
      (value "422K 0.1% 1206")
      (footprint "RESC1206(3216)_N")
      (description "1M5 0.25W 1% 1206 (3216 Metric)  SMD")
      (fields (field (name "TOLERANCE") "1 %") (field (name "POWER") "0.25 W"))
      (libsource (lib "Altium Content Vault") (part "RES"))
    )
    (comp (ref "R46")
      (value "422K 0.1% 1206")
      (footprint "RESC1206(3216)_N")
      (description "1M5 0.25W 1% 1206 (3216 Metric)  SMD")
      (fields (field (name "TOLERANCE") "1 %") (field (name "POWER") "0.25 W"))
      (libsource (lib "Altium Content Vault") (part "RES"))
    )
    (comp (ref "R47")
      (value "422K 0.1% 1206")
      (footprint "RESC1206(3216)_N")
      (description "1M5 0.25W 1% 1206 (3216 Metric)  SMD")
      (fields (field (name "TOLERANCE") "1 %") (field (name "POWER") "0.25 W"))
      (libsource (lib "Altium Content Vault") (part "RES"))
    )
    (comp (ref "R49")
      (value "499R 0.1%")
      (footprint "RESC1608X55X30LL20T20")
      (description "Res Thin Film 0603 499 Ohm 0.1% 1/10W ±25ppm/°C Molded SMD SMD Punched Carrier T/R")
      (fields (field (name "PART NUMBER") "ERA3AEB4990V") (field (name "MANUFACTURER") "Panasonic"))
      (libsource (lib "Altium Content Vault") (part "RES"))
    )
    (comp (ref "R52")
      (value "422K 0.1% 1206")
      (footprint "RESC1206(3216)_N")
      (description "1M5 0.25W 1% 1206 (3216 Metric)  SMD")
      (fields (field (name "TOLERANCE") "1 %") (field (name "POWER") "0.25 W"))
      (libsource (lib "Altium Content Vault") (part "RES"))
    )
    (comp (ref "R56")
      (value "422K 0.1% 1206")
      (footprint "RESC1206(3216)_N")
      (description "1M5 0.25W 1% 1206 (3216 Metric)  SMD")
      (fields (field (name "TOLERANCE") "1 %") (field (name "POWER") "0.25 W"))
      (libsource (lib "Altium Content Vault") (part "RES"))
    )
    (comp (ref "R80")
      (value "422K 0.1% 1206")
      (footprint "RESC1206(3216)_N")
      (description "1M5 0.25W 1% 1206 (3216 Metric)  SMD")
      (fields (field (name "TOLERANCE") "1 %") (field (name "POWER") "0.25 W"))
      (libsource (lib "Altium Content Vault") (part "RES"))
    )
    (comp (ref "R83")
      (value "499R 0.1%")
      (footprint "RESC1608X55X30LL20T20")
      (description "Res Thin Film 0603 499 Ohm 0.1% 1/10W ±25ppm/°C Molded SMD SMD Punched Carrier T/R")
      (fields (field (name "PART NUMBER") "ERA3AEB4990V") (field (name "MANUFACTURER") "Panasonic"))
      (libsource (lib "Altium Content Vault") (part "RES"))
    )
    (comp (ref "R89")
      (value "7.5k 0.1% 1206")
      (footprint "RESC3216X50X50NL20T20")
      (fields (field (name "MANUFACTURER") "Susumu") (field (name "PART NUMBER") "RG3216P-1002-B-T5"))
      (libsource (lib "Altium Content Vault") (part "RES"))
    )
    (comp (ref "R90")
      (value "422K 0.1% 1206")
      (footprint "RESC1206(3216)_N")
      (description "1M5 0.25W 1% 1206 (3216 Metric)  SMD")
      (fields (field (name "TOLERANCE") "1 %") (field (name "POWER") "0.25 W"))
      (libsource (lib "Altium Content Vault") (part "RES"))
    )
    (comp (ref "R91")
      (value "422K 0.1% 1206")
      (footprint "RESC1206(3216)_N")
      (description "1M5 0.25W 1% 1206 (3216 Metric)  SMD")
      (fields (field (name "TOLERANCE") "1 %") (field (name "POWER") "0.25 W"))
      (libsource (lib "Altium Content Vault") (part "RES"))
    )
    (comp (ref "R92")
      (value "422K 0.1% 1206")
      (footprint "RESC1206(3216)_N")
      (description "1M5 0.25W 1% 1206 (3216 Metric)  SMD")
      (fields (field (name "TOLERANCE") "1 %") (field (name "POWER") "0.25 W"))
      (libsource (lib "Altium Content Vault") (part "RES"))
    )
    (comp (ref "R93")
      (value "499R 0.1%")
      (footprint "RESC1608X55X30LL20T20")
      (description "Res Thin Film 0603 499 Ohm 0.1% 1/10W ±25ppm/°C Molded SMD SMD Punched Carrier T/R")
      (fields (field (name "PART NUMBER") "ERA3AEB4990V") (field (name "MANUFACTURER") "Panasonic"))
      (libsource (lib "Altium Content Vault") (part "RES"))
    )
    (comp (ref "R94")
      (value "422K 0.1% 1206")
      (footprint "RESC1206(3216)_N")
      (description "1M5 0.25W 1% 1206 (3216 Metric)  SMD")
      (fields (field (name "TOLERANCE") "1 %") (field (name "POWER") "0.25 W"))
      (libsource (lib "Altium Content Vault") (part "RES"))
    )
    (comp (ref "R96")
      (value "422K 0.1% 1206")
      (footprint "RESC1206(3216)_N")
      (description "1M5 0.25W 1% 1206 (3216 Metric)  SMD")
      (fields (field (name "TOLERANCE") "1 %") (field (name "POWER") "0.25 W"))
      (libsource (lib "Altium Content Vault") (part "RES"))
    )
    (comp (ref "R97")
      (value "422K 0.1% 1206")
      (footprint "RESC1206(3216)_N")
      (description "1M5 0.25W 1% 1206 (3216 Metric)  SMD")
      (fields (field (name "TOLERANCE") "1 %") (field (name "POWER") "0.25 W"))
      (libsource (lib "Altium Content Vault") (part "RES"))
    )
    (comp (ref "R98")
      (value "499R 0.1%")
      (footprint "RESC1608X55X30LL20T20")
      (description "Res Thin Film 0603 499 Ohm 0.1% 1/10W ±25ppm/°C Molded SMD SMD Punched Carrier T/R")
      (fields (field (name "PART NUMBER") "ERA3AEB4990V") (field (name "MANUFACTURER") "Panasonic"))
      (libsource (lib "Altium Content Vault") (part "RES"))
    )
    (comp (ref "R101")
      (value "499R 0.1%")
      (footprint "RESC1608X55X30LL20T20")
      (description "Res Thin Film 0603 499 Ohm 0.1% 1/10W ±25ppm/°C Molded SMD SMD Punched Carrier T/R")
      (fields (field (name "PART NUMBER") "ERA3AEB4990V") (field (name "MANUFACTURER") "Panasonic"))
      (libsource (lib "Altium Content Vault") (part "RES"))
    )
    (comp (ref "R102")
      (value "7.5k 0.1% 1206")
      (footprint "RESC3216X50X50NL20T20")
      (fields (field (name "MANUFACTURER") "Susumu") (field (name "PART NUMBER") "RG3216P-1002-B-T5"))
      (libsource (lib "Altium Content Vault") (part "RES"))
    )
    (comp (ref "R110")
      (value "49.9R")
      (footprint "RESC1005X40X25NL05T05")
      (fields (field (name "MANUFACTURER") "Panasonic") (field (name "PART NUMBER") "ERJ-2RKF49R9X"))
      (libsource (lib "Altium Content Vault") (part "RES"))
    )
    (comp (ref "R111")
      (value "29R")
      (footprint "RESC1608X55X30NL20T10")
      (description "RK73B1JTTD103J")
      (fields (field (name "MANUFACTURER") "KOA Speer") (field (name "TOLERANCE") "5%"))
      (libsource (lib "Altium Content Vault") (part "RES"))
    )
    (comp (ref "R112")
      (value "29R")
      (footprint "RESC1608X55X30NL20T10")
      (description "RK73B1JTTD103J")
      (fields (field (name "MANUFACTURER") "KOA Speer") (field (name "TOLERANCE") "5%"))
      (libsource (lib "Altium Content Vault") (part "RES"))
    )
    (comp (ref "R115")
      (value "20K")
      (footprint "RESC1608X55X30NL20T10")
      (description "RK73B1JTTD103J")
      (fields (field (name "MANUFACTURER") "KOA Speer") (field (name "TOLERANCE") "5%"))
      (libsource (lib "Altium Content Vault") (part "RES"))
    )
    (comp (ref "R116")
      (value "4.7K")
      (footprint "RESC1608X55X25ML10T15")
      (fields
        (field (name "MANUFACTURER") "Yageo")
        (field (name "MANUFACTURER PART NUMBER") "RC0603FR-07470RL")
        (field (name "TOLERANCE") "1%")
      )
      (libsource (lib "Altium Content Vault") (part "RES-2"))
    )
    (comp (ref "R119")
      (value "100k")
      (footprint "RESC1608X55X25ML10T15")
      (fields
        (field (name "MANUFACTURER") "Yageo")
        (field (name "MANUFACTURER PART NUMBER") "RC0603JR-071ML")
        (field (name "TOLERANCE") "5%")
      )
      (libsource (lib "Altium Content Vault") (part "RES-2"))
    )
    (comp (ref "R129")
      (value "59K")
      (footprint "RESC1608X55X30NL15T15")
      (fields
        (field (name "MANUFACTURER") "Panasonic")
        (field (name "PART NUMBER") "ERJ-3EKF5902V")
        (field (name "TOLERANCE") "1%")
      )
      (libsource (lib "Altium Content Vault") (part "RES"))
    )
    (comp (ref "R130")
      (value "0.47R")
      (footprint "RESC1608X55X25ML10T15")
      (description "Chip Resistor, 0 Ohm, +/- 5%, 0.1 W, -55 to 155 degC, 0603 (1608 Metric), RoHS, Tape and Reel")
      (fields (field (name "TOLERANCE") "5%") (field (name "MANUFACTURER") "Yageo"))
      (libsource (lib "Altium Content Vault") (part "RES-2"))
    )
    (comp (ref "R131")
      (value "4.99K")
      (footprint "RESC1609X50X30NL10T20")
      (fields
        (field (name "MANUFACTURER") "Vishay Dale")
        (field (name "PART NUMBER") "CRCW06034K99FKTA")
        (field (name "TOLERANCE") "1%")
      )
      (libsource (lib "Altium Content Vault") (part "RES"))
    )
    (comp (ref "R132")
      (value "2.2K")
      (footprint "RESC1608X55X25NL10T15")
      (fields
        (field (name "TOLERANCE") "1%")
        (field (name "MANUFACTURER") "Yageo")
        (field (name "MANUFACTURER PART NUMBER") "RC0603FR-072K2L")
      )
      (libsource (lib "Altium Content Vault") (part "RES-2"))
    )
    (comp (ref "R133")
      (value "180R")
      (footprint "RESC1608X55X25LL10T15")
      (description "Chip Resistor, 180 Ohm, +/- 1%, 0.1 W, -55 to 155 degC, 0603 (1608 Metric), RoHS, Tape and Reel")
      (fields (field (name "TOLERANCE") "1%") (field (name "MANUFACTURER") "Yageo"))
      (libsource (lib "Altium Content Vault") (part "RES-2"))
    )
    (comp (ref "R134")
      (value "10K")
      (footprint "RESC1608X55X30NL20T10")
      (description "RK73B1JTTD103J")
      (fields (field (name "MANUFACTURER") "KOA Speer") (field (name "TOLERANCE") "5%"))
      (libsource (lib "Altium Content Vault") (part "RES"))
    )
    (comp (ref "R135")
      (value "10K")
      (footprint "RESC1608X55X30NL20T10")
      (description "RK73B1JTTD103J")
      (fields (field (name "MANUFACTURER") "KOA Speer") (field (name "TOLERANCE") "5%"))
      (libsource (lib "Altium Content Vault") (part "RES"))
    )
    (comp (ref "R136")
      (value "16.5K")
      (footprint "RESC1608X55X30NL15T15")
      (description "RES, 16K5, 1%, 0.1W, 0603, THICK FILM")
      (fields (field (name "MANUFACTURER") "Panasonic") (field (name "PART NUMBER") "ERJ-3EKF1652V"))
      (libsource (lib "Altium Content Vault") (part "RES"))
    )
    (comp (ref "R137")
      (value "330R")
      (footprint "RESC1608X55X25NL10T15")
      (description "Chip Resistor, 330 Ohm, +/- 1%, 0.1 W, -55 to 155 degC, 0603 (1608 Metric), RoHS, Tape and Reel")
      (fields (field (name "TOLERANCE") "10%"))
      (libsource (lib "Altium Content Vault") (part "RES-2"))
    )
    (comp (ref "R139")
      (value "10K")
      (footprint "RESC1609X55X30LL15T15")
      (description "Chip Resistor, 10 KOhm, +/- 1%, 0.1 W, -55 to 155 degC, 0603 (1608 Metric), RoHS, Tape and Reel")
      (fields (field (name "TOLERANCE") "1%") (field (name "MANUFACTURER") "Panasonic"))
      (libsource (lib "Altium Content Vault") (part "RES-2"))
    )
    (comp (ref "R140")
      (value "33K")
      (footprint "RESC1005X40X25ML05T05")
      (fields
        (field (name "PART NUMBER") "ERJ2RKF3302X")
        (field (name "MANUFACTURER") "Panasonic")
        (field (name "MANUFACTURER PART NUMBER") "ERJ-2RKF3302X")
      )
      (libsource (lib "Altium Content Vault") (part "RES"))
    )
    (comp (ref "R141")
      (value "33K")
      (footprint "RESC1005X40X25ML05T05")
      (fields
        (field (name "PART NUMBER") "ERJ2RKF3302X")
        (field (name "MANUFACTURER") "Panasonic")
        (field (name "MANUFACTURER PART NUMBER") "ERJ-2RKF3302X")
      )
      (libsource (lib "Altium Content Vault") (part "RES"))
    )
    (comp (ref "R142")
      (value "6.2R")
      (footprint "RESC2012X70N")
      (description "Resistor, 0805 SMD, Empty footprint")
      (libsource (lib "") (part "RES_EMPTY_0805_1"))
    )
    (comp (ref "R143")
      (value "330R")
      (footprint "RESC1608X55X25NL10T15")
      (description "Chip Resistor, 330 Ohm, +/- 1%, 0.1 W, -55 to 155 degC, 0603 (1608 Metric), RoHS, Tape and Reel")
      (fields (field (name "TOLERANCE") "10%"))
      (libsource (lib "Altium Content Vault") (part "RES-2"))
    )
    (comp (ref "R172")
      (value "100k")
      (footprint "RESC1608X55X30NL15T15")
      (description "Res Thick Film 0603 100K Ohm 1% 0.1W(1/10W) ±100ppm/C Pad SMD Automotive T/R")
      (fields (field (name "PART NUMBER") "ERJ-3EKF1003V") (field (name "MANUFACTURER") "Panasonic"))
      (libsource (lib "Altium Content Vault") (part "RES"))
    )
    (comp (ref "R173")
      (value "100k")
      (footprint "RESC1608X55X30NL15T15")
      (description "Res Thick Film 0603 100K Ohm 1% 0.1W(1/10W) ±100ppm/C Pad SMD Automotive T/R")
      (fields (field (name "PART NUMBER") "ERJ-3EKF1003V") (field (name "MANUFACTURER") "Panasonic"))
      (libsource (lib "Altium Content Vault") (part "RES"))
    )
    (comp (ref "R174")
      (value "330R")
      (footprint "RESC1608X55X25NL10T15")
      (description "Chip Resistor, 330 Ohm, +/- 1%, 0.1 W, -55 to 155 degC, 0603 (1608 Metric), RoHS, Tape and Reel")
      (fields (field (name "TOLERANCE") "10%"))
      (libsource (lib "Altium Content Vault") (part "RES-2"))
    )
    (comp (ref "R175")
      (value "330R")
      (footprint "RESC1608X55X25NL10T15")
      (description "Chip Resistor, 330 Ohm, +/- 1%, 0.1 W, -55 to 155 degC, 0603 (1608 Metric), RoHS, Tape and Reel")
      (fields (field (name "TOLERANCE") "10%"))
      (libsource (lib "Altium Content Vault") (part "RES-2"))
    )
    (comp (ref "R176")
      (value "100k")
      (footprint "RESC1608X55X30NL15T15")
      (description "Res Thick Film 0603 100K Ohm 1% 0.1W(1/10W) ±100ppm/C Pad SMD Automotive T/R")
      (fields (field (name "PART NUMBER") "ERJ-3EKF1003V") (field (name "MANUFACTURER") "Panasonic"))
      (libsource (lib "Altium Content Vault") (part "RES"))
    )
    (comp (ref "R177")
      (value "75K")
      (footprint "RESC1608X55X30NL15T15")
      (fields
        (field (name "PART NUMBER") "ERJ-3EKF7502V")
        (field (name "MANUFACTURER") "Panasonic")
        (field (name "TOLERANCE") "1%")
      )
      (libsource (lib "Altium Content Vault") (part "RES"))
    )
    (comp (ref "R178")
      (value "15K")
      (footprint "RESC1608X55X30NL20T10")
      (description "RK73B1JTTD103J")
      (fields (field (name "MANUFACTURER") "KOA Speer") (field (name "TOLERANCE") "5%"))
      (libsource (lib "Altium Content Vault") (part "RES"))
    )
    (comp (ref "R179")
      (value "10K")
      (footprint "RESC1608X55X30NL20T10")
      (description "RK73B1JTTD103J")
      (fields (field (name "MANUFACTURER") "KOA Speer") (field (name "TOLERANCE") "5%"))
      (libsource (lib "Altium Content Vault") (part "RES"))
    )
    (comp (ref "R180")
      (value "10K")
      (footprint "RESC1608X55X30NL20T10")
      (description "RK73B1JTTD103J")
      (fields (field (name "MANUFACTURER") "KOA Speer") (field (name "TOLERANCE") "5%"))
      (libsource (lib "Altium Content Vault") (part "RES"))
    )
    (comp (ref "R181")
      (value "30K 0.1%")
      (footprint "RESC1608X55N")
      (description "Resistor, SMD 30 kOhm 0603  ±  0.1 %, ERA3AEB303V, Panasonic Automotive & Industrial Systems")
      (fields (field (name "MANUFACTURER") "Panasonic") (field (name "PART NUMBER") "ERA3AEB303V"))
      (libsource (lib "PBL - Resistors") (part "RES"))
    )
    (comp (ref "R183")
      (value "1K 0.1%")
      (footprint "RESC1608X55X25NL10T15")
      (description "RES SMD 1K OHM 0.1% 1/10W 0603")
      (fields (field (name "PART NUMBER") "RT0603BRE071KL") (field (name "MANUFACTURER") "Yageo"))
      (libsource (lib "Altium Content Vault") (part "RES"))
    )
    (comp (ref "R184")
      (value "499R 0.1%")
      (footprint "RESC1608X55N")
      (description "Res Thin Film 0603 499 Ohm 0.1% 1/10W ±25ppm/°C Molded SMD SMD Punched Carrier T/R")
      (fields (field (name "PART NUMBER") "ERA3AEB4990V") (field (name "MANUFACTURER") "Panasonic"))
      (libsource (lib "PBL - Resistors") (part "RES"))
    )
    (comp (ref "R185")
      (value "49.9R")
      (footprint "RESC1005X40X25NL05T05")
      (fields (field (name "MANUFACTURER") "Panasonic") (field (name "PART NUMBER") "ERJ-2RKF49R9X"))
      (libsource (lib "Altium Content Vault") (part "RES"))
    )
    (comp (ref "R186")
      (value "100k")
      (footprint "RESC1608X55X30NL15T15")
      (description "Res Thick Film 0603 100K Ohm 1% 0.1W(1/10W) ±100ppm/C Pad SMD Automotive T/R")
      (fields (field (name "PART NUMBER") "ERJ-3EKF1003V") (field (name "MANUFACTURER") "Panasonic"))
      (libsource (lib "Altium Content Vault") (part "RES"))
    )
    (comp (ref "R187")
      (value "1K 0.1%")
      (footprint "RESC1608X55X25NL10T15")
      (description "RES SMD 1K OHM 0.1% 1/10W 0603")
      (fields (field (name "PART NUMBER") "RT0603BRE071KL") (field (name "MANUFACTURER") "Yageo"))
      (libsource (lib "Altium Content Vault") (part "RES"))
    )
    (comp (ref "R188")
      (value "499R 0.1%")
      (footprint "RESC1608X55N")
      (description "Res Thin Film 0603 499 Ohm 0.1% 1/10W ±25ppm/°C Molded SMD SMD Punched Carrier T/R")
      (fields (field (name "PART NUMBER") "ERA3AEB4990V") (field (name "MANUFACTURER") "Panasonic"))
      (libsource (lib "PBL - Resistors") (part "RES"))
    )
    (comp (ref "R189")
      (value "30K 0.1%")
      (footprint "RESC1608X55N")
      (description "Resistor, SMD 30 kOhm 0603  ±  0.1 %, ERA3AEB303V, Panasonic Automotive & Industrial Systems")
      (fields (field (name "MANUFACTURER") "Panasonic") (field (name "PART NUMBER") "ERA3AEB303V"))
      (libsource (lib "PBL - Resistors") (part "RES"))
    )
    (comp (ref "R190")
      (value "100k")
      (footprint "RESC1608X55X30NL15T15")
      (description "Res Thick Film 0603 100K Ohm 1% 0.1W(1/10W) ±100ppm/C Pad SMD Automotive T/R")
      (fields (field (name "PART NUMBER") "ERJ-3EKF1003V") (field (name "MANUFACTURER") "Panasonic"))
      (libsource (lib "Altium Content Vault") (part "RES"))
    )
    (comp (ref "R191")
      (value "180R")
      (footprint "RESC1608X55X25LL10T15")
      (description "Chip Resistor, 180 Ohm, +/- 1%, 0.1 W, -55 to 155 degC, 0603 (1608 Metric), RoHS, Tape and Reel")
      (fields (field (name "TOLERANCE") "1%") (field (name "MANUFACTURER") "Yageo"))
      (libsource (lib "Altium Content Vault") (part "RES-2"))
    )
    (comp (ref "R192")
      (value "16.5K")
      (footprint "RESC1608X55X30NL15T15")
      (description "RES, 16K5, 1%, 0.1W, 0603, THICK FILM")
      (fields (field (name "MANUFACTURER") "Panasonic") (field (name "PART NUMBER") "ERJ-3EKF1652V"))
      (libsource (lib "Altium Content Vault") (part "RES"))
    )
    (comp (ref "R193")
      (value "10K")
      (footprint "RESC1609X55X30NL15T15")
      (description "Chip Resistor, 10 KOhm, +/- 1%, 0.1 W, -55 to 155 degC, 0603 (1608 Metric), RoHS, Tape and Reel")
      (fields (field (name "TOLERANCE") "1%") (field (name "MANUFACTURER") "Panasonic"))
      (libsource (lib "Altium Content Vault") (part "RES-2"))
    )
    (comp (ref "R194")
      (value "7.5k 0.1% 1206")
      (footprint "RESC3216X50X50NL20T20")
      (fields (field (name "MANUFACTURER") "Susumu") (field (name "PART NUMBER") "RG3216P-1002-B-T5"))
      (libsource (lib "Altium Content Vault") (part "RES"))
    )
    (comp (ref "R198")
      (value "49.9R")
      (footprint "RESC1005X40X25NL05T05")
      (fields (field (name "MANUFACTURER") "Panasonic") (field (name "PART NUMBER") "ERJ-2RKF49R9X"))
      (libsource (lib "Altium Content Vault") (part "RES"))
    )
    (comp (ref "R199")
      (value "49.9R")
      (footprint "RESC1005X40X25NL05T05")
      (fields (field (name "MANUFACTURER") "Panasonic") (field (name "PART NUMBER") "ERJ-2RKF49R9X"))
      (libsource (lib "Altium Content Vault") (part "RES"))
    )
    (comp (ref "R200")
      (value "49.9R")
      (footprint "RESC1005X40X25NL05T05")
      (fields (field (name "MANUFACTURER") "Panasonic") (field (name "PART NUMBER") "ERJ-2RKF49R9X"))
      (libsource (lib "Altium Content Vault") (part "RES"))
    )
    (comp (ref "R201")
      (value "0R")
      (footprint "RESC1005X40X25NL05T05")
      (fields (field (name "MANUFACTURER") "Panasonic") (field (name "PART NUMBER") "ERJ-2RKF49R9X"))
      (libsource (lib "Altium Content Vault") (part "RES"))
    )
    (comp (ref "R202")
      (value "1K 0.1%")
      (footprint "RESC1608X55X30LL20T20")
      (fields
        (field (name "MANUFACTURER") "Panasonic")
        (field (name "PART NUMBER") "ERA3AEB102V")
        (field (name "MANUFACTURER PART NUMBER") "ERA-3AEB102V")
      )
      (libsource (lib "Altium Content Vault") (part "RES"))
    )
    (comp (ref "R203")
      (value "1.65K 0.1%")
      (footprint "RESC1608X55X30LL20T20")
      (fields
        (field (name "PART NUMBER") "ERA3AEB1651V")
        (field (name "MANUFACTURER") "Panasonic")
        (field (name "MANUFACTURER PART NUMBER") "ERA-3AEB1651V")
      )
      (libsource (lib "Altium Content Vault") (part "RES"))
    )
    (comp (ref "R204")
      (value "180R")
      (footprint "RESC1608X55X25LL10T15")
      (description "Chip Resistor, 180 Ohm, +/- 1%, 0.1 W, -55 to 155 degC, 0603 (1608 Metric), RoHS, Tape and Reel")
      (fields (field (name "TOLERANCE") "1%") (field (name "MANUFACTURER") "Yageo"))
      (libsource (lib "Altium Content Vault") (part "RES-2"))
    )
    (comp (ref "R205")
      (value "59R")
      (footprint "RESC1608X55X30ML15T15")
      (fields
        (field (name "MANUFACTURER") "Panasonic")
        (field (name "PART NUMBER") "ERJ-3EKF59R0V")
        (field (name "TOLERANCE") "1%")
      )
      (libsource (lib "Altium Content Vault") (part "RES"))
    )
    (comp (ref "R206")
      (value "1K")
      (footprint "RESC1608X55X30NL20T10")
      (description "RK73B1JTTD103J")
      (fields (field (name "MANUFACTURER") "KOA Speer") (field (name "TOLERANCE") "5%"))
      (libsource (lib "Altium Content Vault") (part "RES"))
    )
    (comp (ref "R207")
      (value "0R")
      (footprint "RESC1005X40X25NL05T05")
      (fields (field (name "MANUFACTURER") "Panasonic") (field (name "PART NUMBER") "ERJ-2RKF49R9X"))
      (libsource (lib "Altium Content Vault") (part "RES"))
    )
    (comp (ref "R209")
      (value "0.47R")
      (footprint "RESC1608X55X25ML10T15")
      (description "Chip Resistor, 0 Ohm, +/- 5%, 0.1 W, -55 to 155 degC, 0603 (1608 Metric), RoHS, Tape and Reel")
      (fields (field (name "TOLERANCE") "5%") (field (name "MANUFACTURER") "Yageo"))
      (libsource (lib "Altium Content Vault") (part "RES-2"))
    )
    (comp (ref "R216")
      (value "0R")
      (footprint "RESC1608X55X25NL10T15")
      (description "Chip Resistor, 0 Ohm, +/- 5%, 0.1 W, -55 to 155 degC, 0603 (1608 Metric), RoHS, Tape and Reel")
      (fields (field (name "TOLERANCE") "5%") (field (name "MANUFACTURER") "Yageo"))
      (libsource (lib "Altium Content Vault") (part "RES-2"))
    )
    (comp (ref "U14")
      (value "TS431BILT")
      (footprint "SOT23-5")
      (description "30mA, Low voltage adjustable shunt reference, 1.24 to 6V, 5-Pin SOT23-5, Tape and Reel")
      (libsource (lib "PBL - Integrated Circuits") (part "PM-REF-431-IL5"))
    )
    (comp (ref "U15")
      (value "74AHC1G08SE-7")
      (footprint "DCK0005A_M")
      (description "Single 2-Input Positive-AND Gate, DCK0005A, SMALL T&R")
      (fields
        (field (name "GENERIC PART NUMBER") "SN74AHC1G08")
        (field (name "MANUFACTURER") "Texas Instruments")
      )
      (libsource (lib "Altium Content Vault") (part "TI-SN74XXX1X08-5"))
    )
    (comp (ref "U16")
      (value "1EDN8550B")
      (footprint "SOT23-6")
      (description "Single-channel EiceDRIVER™ with true  differential inputs")
      (libsource (lib "1EDN8550B") (part "1EDN8550B"))
    )
    (comp (ref "U17")
      (value "MCP6V96T")
      (footprint "DCK0005A_N")
      (fields (field (name "PARTNUMBER") "OPA348AIDCKT") (field (name "MANUFACTURER") "Texas Instruments"))
      (libsource (lib "Altium Content Vault") (part "TI-AMP-S3-2-5"))
    )
    (comp (ref "U18")
      (value "TS431BILT")
      (footprint "SOT23-5")
      (description "30mA, Low voltage adjustable shunt reference, 1.24 to 6V, 5-Pin SOT23-5, Tape and Reel")
      (libsource (lib "PBL - Integrated Circuits") (part "PM-REF-431-IL5"))
    )
    (comp (ref "U19")
      (value "MCP6L72T-E/SN")
      (footprint "SOP65P490X109-8N")
      (description "2.8 MHz, 150 渭A Dual Op Amp, 8-Pin SOIC, Extended Temperature Range, Tape and Reel")
      (libsource (lib "PBL - Integrated Circuits") (part "AMP-OPA-MCP602-IL8"))
    )
    (comp (ref "U20")
      (value "STM32G491CCU")
      (footprint "QFN50P700X700X65-49N-D")
      (fields
        (field (name "MANUFACTURER") "STMicroelectronics")
        (field (name "MANUFACTURER PART NUMBER") "STM32G491CCU6")
        (field (name "SUPPLIER PART NUMBER 1") "497-STM32G491CCU6-ND")
      )
      (libsource (lib "SamacSys") (part "STM32G491CCU"))
    )
    (comp (ref "U21")
      (value "TLV9051IDBVR")
      (footprint "SOT23-5")
      (description "2.8 MHz, 150 渭A Op Amp, 5-Pin SOT-23, Extended Temperature Range, Tape and Reel")
      (libsource (lib "PBL - Integrated Circuits") (part "AMP-OPA-MCP601-SOT5"))
    )
    (comp (ref "U22")
      (value "TS431BILT")
      (footprint "SOT23-5")
      (description "30mA, Low voltage adjustable shunt reference, 1.24 to 6V, 5-Pin SOT23-5, Tape and Reel")
      (libsource (lib "PBL - Integrated Circuits") (part "PM-REF-431-IL5"))
    )
  )
  (nets
    (net (code "1") (name "/ADC1_IN4") (class "Default")
      (node (ref "C126") (pin "2") (pinfunction "2_2") (pintype "passive"))
      (node (ref "R185") (pin "2") (pinfunction "2_2") (pintype "passive"))
      (node (ref "U20") (pin "11") (pinfunction "PA3_11") (pintype "passive"))
    )
    (net (code "2") (name "/ADC1_IN5") (class "Default")
      (node (ref "C151") (pin "2") (pinfunction "2_2") (pintype "passive"))
      (node (ref "R200") (pin "2") (pinfunction "2_2") (pintype "passive"))
      (node (ref "U20") (pin "27") (pinfunction "PB14_27") (pintype "passive"))
    )
    (net (code "3") (name "/ADC2_IN4") (class "Default")
      (node (ref "C144") (pin "1") (pinfunction "1_1") (pintype "passive"))
      (node (ref "C149") (pin "2") (pinfunction "2_2") (pintype "passive"))
      (node (ref "R198") (pin "2") (pinfunction "2_2") (pintype "passive"))
      (node (ref "U20") (pin "15") (pinfunction "PA7_15") (pintype "passive"))
    )
    (net (code "4") (name "/ADC2_IN5") (class "Default")
      (node (ref "C149") (pin "1") (pinfunction "1_1") (pintype "passive"))
      (node (ref "C150") (pin "2") (pinfunction "2_2") (pintype "passive"))
      (node (ref "R199") (pin "2") (pinfunction "2_2") (pintype "passive"))
      (node (ref "U20") (pin "16") (pinfunction "PC4_16") (pintype "passive"))
    )
    (net (code "5") (name "/DAC1") (class "Default")
      (node (ref "C123") (pin "2") (pinfunction "2_2") (pintype "passive"))
      (node (ref "C145") (pin "2") (pinfunction "2_2") (pintype "passive"))
      (node (ref "C50") (pin "2") (pinfunction "2_2") (pintype "passive"))
      (node (ref "R181") (pin "2") (pinfunction "2_2") (pintype "passive"))
      (node (ref "R207") (pin "2") (pinfunction "2_2") (pintype "passive"))
      (node (ref "R40") (pin "1") (pinfunction "1_1") (pintype "passive"))
      (node (ref "R89") (pin "1") (pinfunction "1_1") (pintype "passive"))
    )
    (net (code "6") (name "/DRV_TOP_LF_MOS") (class "Default")
      (node (ref "R175") (pin "1") (pinfunction "1_1") (pintype "passive"))
      (node (ref "U20") (pin "32") (pinfunction "PA10_32") (pintype "passive"))
    )
    (net (code "7") (name "/EN_DCDC_BOOST") (class "Default")
      (node (ref "IC6") (pin "3") (pinfunction "EN_3") (pintype "passive"))
      (node (ref "R172") (pin "2") (pinfunction "2_2") (pintype "passive"))
      (node (ref "U20") (pin "12") (pinfunction "PA4_12") (pintype "passive"))
    )
    (net (code "8") (name "/GRID_VAC_OPAMP2_IN+") (class "Default")
      (node (ref "C60") (pin "1") (pinfunction "1_1") (pintype "passive"))
      (node (ref "R101") (pin "2") (pinfunction "2_2") (pintype "passive"))
      (node (ref "U20") (pin "17") (pinfunction "PB0_17") (pintype "passive"))
      (node (ref "U20") (pin "19") (pinfunction "PB2_19") (pintype "passive"))
    )
    (net (code "9") (name "/GRID_VAC_OPAMP2_OUT") (class "Default")
      (node (ref "R198") (pin "1") (pinfunction "1_1") (pintype "passive"))
      (node (ref "U20") (pin "14") (pinfunction "PA6_14") (pintype "passive"))
    )
    (net (code "10") (name "/GRID_VAC_OPAMP3_OUT") (class "Default")
      (node (ref "R199") (pin "1") (pinfunction "1_1") (pintype "passive"))
      (node (ref "U20") (pin "18") (pinfunction "PB1_18") (pintype "passive"))
    )
    (net (code "11") (name "/IAC_COMP3_INP") (class "Default")
      (node (ref "R216") (pin "2") (pinfunction "2_2") (pintype "passive"))
      (node (ref "U20") (pin "8") (pinfunction "PA0_8") (pintype "passive"))
      (node (ref "U20") (pin "9") (pinfunction "PA1_9") (pintype "passive"))
    )
    (net (code "12") (name "/IAC_OPAMP1_OUT") (class "Default")
      (node (ref "R185") (pin "1") (pinfunction "1_1") (pintype "passive"))
      (node (ref "U20") (pin "10") (pinfunction "PA2_10") (pintype "passive"))
    )
    (net (code "13") (name "/INV_RTN_SHUNT+") (class "Default")
      (node (ref "R183") (pin "1") (pinfunction "1_1") (pintype "passive"))
    )
    (net (code "14") (name "/INV_RTN_SHUNT-") (class "Default")
      (node (ref "R187") (pin "1") (pinfunction "1_1") (pintype "passive"))
    )
    (net (code "15") (name "/LF_TOP_TRIG_ADC") (class "Default")
      (node (ref "U20") (pin "33") (pinfunction "PA11_33") (pintype "passive"))
    )
    (net (code "16") (name "/L_GRID") (class "Default")
      (node (ref "R45") (pin "2") (pinfunction "2_2") (pintype "passive"))
    )
    (net (code "17") (name "/L_GRID_BF_RELAY") (class "Default")
      (node (ref "R90") (pin "2") (pinfunction "2_2") (pintype "passive"))
    )
    (net (code "18") (name "/NCHP_TIM8_CH1") (class "Default")
      (node (ref "R137") (pin "1") (pinfunction "1_1") (pintype "passive"))
      (node (ref "U20") (pin "45") (pinfunction "PB7_45") (pintype "passive"))
    )
    (net (code "19") (name "/NRST") (class "Default")
      (node (ref "C72") (pin "2") (pinfunction "2_2") (pintype "passive"))
      (node (ref "J3") (pin "5") (pinfunction "5_5") (pintype "passive"))
      (node (ref "P4") (pin "5") (pinfunction "5_5") (pintype "passive"))
      (node (ref "U20") (pin "7") (pinfunction "PG10-NRST_7") (pintype "passive"))
    )
    (net (code "20") (name "/N_GRID") (class "Default")
      (node (ref "R52") (pin "2") (pinfunction "2_2") (pintype "passive"))
    )
    (net (code "21") (name "/N_GRID_BF_RELAY") (class "Default")
      (node (ref "R94") (pin "2") (pinfunction "2_2") (pintype "passive"))
    )
    (net (code "22") (name "/OPAMP3_IN+") (class "Default")
      (node (ref "C156") (pin "2") (pinfunction "2_2") (pintype "passive"))
      (node (ref "R201") (pin "2") (pinfunction "2_2") (pintype "passive"))
      (node (ref "U20") (pin "26") (pinfunction "PB13_26") (pintype "passive"))
    )
    (net (code "23") (name "/SPI_MISO_TOP_LF_MOS") (class "Default")
      (node (ref "U20") (pin "42") (pinfunction "PB4_42") (pintype "passive"))
    )
    (net (code "24") (name "/SPI_MOSI_TOP_LF_MOS") (class "Default")
      (node (ref "U20") (pin "43") (pinfunction "PB5_43") (pintype "passive"))
    )
    (net (code "25") (name "/SPI_SCK_TOP_LF_MOS") (class "Default")
      (node (ref "U20") (pin "41") (pinfunction "PB3_41") (pintype "passive"))
    )
    (net (code "26") (name "/STATUS1") (class "Default")
      (node (ref "Q19") (pin "1") (pinfunction "G_1") (pintype "passive"))
      (node (ref "R119") (pin "2") (pinfunction "2_2") (pintype "passive"))
      (node (ref "U20") (pin "31") (pinfunction "PA9_31") (pintype "passive"))
    )
    (net (code "27") (name "/SWCLK") (class "Default")
      (node (ref "J3") (pin "2") (pinfunction "2_2") (pintype "passive"))
      (node (ref "P4") (pin "2") (pinfunction "2_2") (pintype "passive"))
      (node (ref "R111") (pin "2") (pinfunction "2_2") (pintype "passive"))
    )
    (net (code "28") (name "/SWDIO") (class "Default")
      (node (ref "J3") (pin "4") (pinfunction "4_4") (pintype "passive"))
      (node (ref "P4") (pin "4") (pinfunction "4_4") (pintype "passive"))
      (node (ref "R112") (pin "2") (pinfunction "2_2") (pintype "passive"))
    )
    (net (code "29") (name "/TMON_NTC") (class "Default")
      (node (ref "C127") (pin "2") (pinfunction "2_2") (pintype "passive"))
      (node (ref "NTC4") (pin "2") (pinfunction "2_2") (pintype "passive"))
      (node (ref "R186") (pin "1") (pinfunction "1_1") (pintype "passive"))
      (node (ref "U20") (pin "28") (pinfunction "PB15_28") (pintype "passive"))
    )
    (net (code "30") (name "/TOP_LF_TWO_LEVEL_TIM1_CH2") (class "Default")
      (node (ref "R143") (pin "1") (pinfunction "1_1") (pintype "passive"))
      (node (ref "U20") (pin "30") (pinfunction "PA8_30") (pintype "passive"))
    )
    (net (code "31") (name "/TOP_LF_TWO_LEVEL_TIM1_CH2N") (class "Default")
      (node (ref "R174") (pin "1") (pinfunction "1_1") (pintype "passive"))
      (node (ref "U20") (pin "2") (pinfunction "PC13_2") (pintype "passive"))
    )
    (net (code "32") (name "/VAC_OPAMP6_IN+") (class "Default")
      (node (ref "C148") (pin "2") (pinfunction "2_2") (pintype "passive"))
      (node (ref "R110") (pin "2") (pinfunction "2_2") (pintype "passive"))
      (node (ref "U20") (pin "25") (pinfunction "PB12_25") (pintype "passive"))
    )
    (net (code "33") (name "/VAC_OPAMP6_OUT") (class "Default")
      (node (ref "R200") (pin "1") (pinfunction "1_1") (pintype "passive"))
      (node (ref "U20") (pin "24") (pinfunction "PB11_24") (pintype "passive"))
    )
    (net (code "34") (name "/VDDB_TOP_LF_MOS") (class "Default")
      (node (ref "FB8") (pin "1") (pinfunction "1_1") (pintype "passive"))
    )
    (net (code "35") (name "/VH_TOP_LF_MOS") (class "Default")
      (node (ref "C113") (pin "1") (pintype "passive"))
      (node (ref "R16") (pin "2") (pinfunction "2_2") (pintype "passive"))
    )
    (net (code "36") (name "/VL_TOP_LF_MOS") (class "Default")
      (node (ref "R18") (pin "2") (pinfunction "2_2") (pintype "passive"))
    )
    (net (code "38") (name "/VMON_MOS_DRV_N") (class "Default")
      (node (ref "C163") (pin "2") (pinfunction "2_2") (pintype "passive"))
      (node (ref "R115") (pin "1") (pinfunction "1_1") (pintype "passive"))
      (node (ref "R178") (pin "1") (pinfunction "1_1") (pintype "passive"))
      (node (ref "R179") (pin "2") (pinfunction "2_2") (pintype "passive"))
      (node (ref "U20") (pin "5") (pinfunction "PF0-OSC_IN_5") (pintype "passive"))
    )
    (net (code "39") (name "/VMON_MOS_DRV_P") (class "Default")
      (node (ref "C65") (pin "2") (pinfunction "2_2") (pintype "passive"))
      (node (ref "R177") (pin "2") (pinfunction "2_2") (pintype "passive"))
      (node (ref "R180") (pin "1") (pinfunction "1_1") (pintype "passive"))
      (node (ref "U20") (pin "6") (pinfunction "PF1-OSC_OUT_6") (pintype "passive"))
    )
    (net (code "40") (name "Net-(C51-Pad1)") (class "Default")
      (node (ref "C51") (pin "1") (pinfunction "1_1") (pintype "passive"))
      (node (ref "R102") (pin "2") (pinfunction "2_2") (pintype "passive"))
      (node (ref "R97") (pin "1") (pinfunction "1_1") (pintype "passive"))
      (node (ref "R98") (pin "1") (pinfunction "1_1") (pintype "passive"))
    )
    (net (code "41") (name "Net-(C51-Pad2)") (class "Default")
      (node (ref "C51") (pin "2") (pinfunction "2_2") (pintype "passive"))
      (node (ref "R89") (pin "2") (pinfunction "2_2") (pintype "passive"))
      (node (ref "R92") (pin "1") (pinfunction "1_1") (pintype "passive"))
      (node (ref "R93") (pin "1") (pinfunction "1_1") (pintype "passive"))
    )
    (net (code "42") (name "Net-(C96-Pad1)") (class "Default")
      (node (ref "C96") (pin "1") (pinfunction "1_1") (pintype "passive"))
      (node (ref "R130") (pin "2") (pinfunction "2_2") (pintype "passive"))
    )
    (net (code "43") (name "Net-(C113-Pad2)") (class "Default")
      (node (ref "C113") (pin "2") (pintype "passive"))
      (node (ref "R142") (pin "2") (pinfunction "2_2") (pintype "passive"))
    )
    (net (code "44") (name "Net-(C124-Pad1)") (class "Default")
      (node (ref "C124") (pin "1") (pinfunction "1_1") (pintype "passive"))
      (node (ref "R187") (pin "2") (pinfunction "2_2") (pintype "passive"))
      (node (ref "R188") (pin "1") (pinfunction "1_1") (pintype "passive"))
      (node (ref "R189") (pin "1") (pinfunction "1_1") (pintype "passive"))
    )
    (net (code "45") (name "Net-(C124-Pad2)") (class "Default")
      (node (ref "C124") (pin "2") (pinfunction "2_2") (pintype "passive"))
      (node (ref "R181") (pin "1") (pinfunction "1_1") (pintype "passive"))
      (node (ref "R183") (pin "2") (pinfunction "2_2") (pintype "passive"))
      (node (ref "R184") (pin "1") (pinfunction "1_1") (pintype "passive"))
    )
    (net (code "46") (name "Net-(C146-Pad1)") (class "Default")
      (node (ref "C146") (pin "1") (pinfunction "1_1") (pintype "passive"))
      (node (ref "R194") (pin "2") (pinfunction "2_2") (pintype "passive"))
      (node (ref "R80") (pin "1") (pinfunction "1_1") (pintype "passive"))
      (node (ref "R83") (pin "1") (pinfunction "1_1") (pintype "passive"))
    )
    (net (code "47") (name "Net-(C146-Pad2)") (class "Default")
      (node (ref "C146") (pin "2") (pinfunction "2_2") (pintype "passive"))
      (node (ref "R40") (pin "2") (pinfunction "2_2") (pintype "passive"))
      (node (ref "R47") (pin "1") (pinfunction "1_1") (pintype "passive"))
      (node (ref "R49") (pin "1") (pinfunction "1_1") (pintype "passive"))
    )
    (net (code "48") (name "Net-(C160-Pad1)") (class "Default")
      (node (ref "C160") (pin "1") (pinfunction "1_1") (pintype "passive"))
      (node (ref "R209") (pin "2") (pinfunction "2_2") (pintype "passive"))
    )
    (net (code "49") (name "Net-(D11-K)") (class "Default")
      (node (ref "D11") (pin "1") (pinfunction "K_1") (pintype "passive"))
      (node (ref "R112") (pin "1") (pinfunction "1_1") (pintype "passive"))
      (node (ref "U20") (pin "36") (pinfunction "PA13_36") (pintype "passive"))
    )
    (net (code "50") (name "Net-(D12-K)") (class "Default")
      (node (ref "D12") (pin "1") (pinfunction "K_1") (pintype "passive"))
      (node (ref "R111") (pin "1") (pinfunction "1_1") (pintype "passive"))
      (node (ref "U20") (pin "37") (pinfunction "PA14_37") (pintype "passive"))
    )
    (net (code "51") (name "Net-(D22-K{slash}A)") (class "Default")
      (node (ref "C108") (pin "1") (pinfunction "1_1") (pintype "passive"))
      (node (ref "D22") (pin "3") (pinfunction "K/A_3") (pintype "passive"))
    )
    (net (code "52") (name "Net-(D30-A)") (class "Default")
      (node (ref "C123") (pin "1") (pinfunction "1_1") (pintype "passive"))
      (node (ref "D30") (pin "1") (pinfunction "A_1") (pintype "passive"))
      (node (ref "D30") (pin "2") (pinfunction "K_2") (pintype "passive"))
      (node (ref "R184") (pin "2") (pinfunction "2_2") (pintype "passive"))
      (node (ref "U17") (pin "1") (pinfunction "IN+_1") (pintype "input"))
    )
    (net (code "53") (name "Net-(D30-K{slash}A)") (class "Default")
      (node (ref "C125") (pin "1") (pinfunction "1_1") (pintype "passive"))
      (node (ref "D30") (pin "3") (pinfunction "K/A_3") (pintype "passive"))
      (node (ref "R188") (pin "2") (pinfunction "2_2") (pintype "passive"))
      (node (ref "U17") (pin "3") (pinfunction "IN-_3") (pintype "input"))
    )
    (net (code "54") (name "Net-(D31-A)") (class "Default")
      (node (ref "C50") (pin "1") (pinfunction "1_1") (pintype "passive"))
      (node (ref "D31") (pin "1") (pinfunction "A_1") (pintype "passive"))
      (node (ref "D31") (pin "2") (pinfunction "K_2") (pintype "passive"))
      (node (ref "R93") (pin "2") (pinfunction "2_2") (pintype "passive"))
      (node (ref "U19") (pin "3") (pinfunction "VINA+_3") (pintype "input"))
    )
    (net (code "55") (name "Net-(D31-K{slash}A)") (class "Default")
      (node (ref "C52") (pin "1") (pinfunction "1_1") (pintype "passive"))
      (node (ref "D31") (pin "3") (pinfunction "K/A_3") (pintype "passive"))
      (node (ref "R98") (pin "2") (pinfunction "2_2") (pintype "passive"))
      (node (ref "U19") (pin "2") (pinfunction "VINA-_2") (pintype "input"))
    )
    (net (code "56") (name "Net-(D32-A)") (class "Default")
      (node (ref "C145") (pin "1") (pinfunction "1_1") (pintype "passive"))
      (node (ref "D32") (pin "1") (pinfunction "A_1") (pintype "passive"))
      (node (ref "D32") (pin "2") (pinfunction "K_2") (pintype "passive"))
      (node (ref "R49") (pin "2") (pinfunction "2_2") (pintype "passive"))
      (node (ref "U19") (pin "5") (pinfunction "VINB+_5") (pintype "input"))
    )
    (net (code "57") (name "Net-(D32-K{slash}A)") (class "Default")
      (node (ref "C147") (pin "1") (pinfunction "1_1") (pintype "passive"))
      (node (ref "D32") (pin "3") (pinfunction "K/A_3") (pintype "passive"))
      (node (ref "R83") (pin "2") (pinfunction "2_2") (pintype "passive"))
      (node (ref "U19") (pin "6") (pinfunction "VINB-_6") (pintype "input"))
    )
    (net (code "58") (name "Net-(IC6-FB)") (class "Default")
      (node (ref "IC6") (pin "6") (pinfunction "FB_6") (pintype "passive"))
      (node (ref "R129") (pin "1") (pinfunction "1_1") (pintype "passive"))
      (node (ref "R131") (pin "2") (pinfunction "2_2") (pintype "passive"))
    )
    (net (code "59") (name "Net-(IC6-OUT)") (class "Default")
      (node (ref "C102") (pin "2") (pinfunction "2_2") (pintype "passive"))
      (node (ref "FB19") (pin "1") (pinfunction "1_1") (pintype "passive"))
      (node (ref "IC6") (pin "1") (pinfunction "OUT_1") (pintype "passive"))
      (node (ref "R129") (pin "2") (pinfunction "2_2") (pintype "passive"))
    )
    (net (code "60") (name "Net-(IC6-SW)") (class "Default")
      (node (ref "IC6") (pin "7") (pinfunction "SW_7") (pintype "passive"))
      (node (ref "L5") (pin "2") (pinfunction "2_2") (pintype "passive"))
    )
    (net (code "61") (name "Net-(LED3-K)") (class "Default")
      (node (ref "LED3") (pin "1") (pinfunction "K_1") (pintype "passive"))
      (node (ref "R116") (pin "2") (pinfunction "2_2") (pintype "passive"))
    )
    (net (code "62") (name "Net-(Q13-B)") (class "Default")
      (node (ref "C107") (pin "2") (pinfunction "2_2") (pintype "passive"))
      (node (ref "Q13") (pin "1") (pinfunction "B_1") (pintype "passive"))
      (node (ref "R133") (pin "1") (pinfunction "1_1") (pintype "passive"))
      (node (ref "U14") (pin "3") (pinfunction "K_3") (pintype "passive"))
    )
    (net (code "63") (name "Net-(Q13-E)") (class "Default")
      (node (ref "C110") (pin "2") (pinfunction "2_2") (pintype "passive"))
      (node (ref "FB12") (pin "2") (pinfunction "2_2") (pintype "passive"))
      (node (ref "Q13") (pin "2") (pinfunction "E_2") (pintype "passive"))
      (node (ref "R136") (pin "2") (pinfunction "2_2") (pintype "passive"))
    )
    (net (code "64") (name "Net-(Q14A-B)") (class "Default")
      (node (ref "Q14") (pin "5") (pinfunction "B_5") (pintype "passive"))
      (node (ref "R134") (pin "2") (pinfunction "2_2") (pintype "passive"))
    )
    (net (code "65") (name "Net-(Q14A-C)") (class "Default")
      (node (ref "C108") (pin "2") (pinfunction "2_2") (pintype "passive"))
      (node (ref "Q14") (pin "3") (pinfunction "C_3") (pintype "passive"))
      (node (ref "Q14") (pin "6") (pinfunction "C_6") (pintype "passive"))
    )
    (net (code "66") (name "Net-(Q14A-E)") (class "Default")
      (node (ref "C106") (pin "2") (pinfunction "2_2") (pintype "passive"))
      (node (ref "FB10") (pin "1") (pinfunction "1_1") (pintype "passive"))
      (node (ref "Q14") (pin "4") (pinfunction "E_4") (pintype "passive"))
      (node (ref "R132") (pin "2") (pinfunction "2_2") (pintype "passive"))
    )
    (net (code "67") (name "Net-(Q14B-B)") (class "Default")
      (node (ref "Q14") (pin "2") (pinfunction "B_2") (pintype "passive"))
      (node (ref "R135") (pin "2") (pinfunction "2_2") (pintype "passive"))
    )
    (net (code "68") (name "Net-(Q15-D)") (class "Default")
      (node (ref "Q15") (pin "3") (pinfunction "D_3") (pintype "passive"))
      (node (ref "R132") (pin "1") (pinfunction "1_1") (pintype "passive"))
      (node (ref "R134") (pin "1") (pinfunction "1_1") (pintype "passive"))
      (node (ref "R135") (pin "1") (pinfunction "1_1") (pintype "passive"))
    )
    (net (code "69") (name "Net-(Q15-G)") (class "Default")
      (node (ref "Q15") (pin "1") (pinfunction "G_1") (pintype "passive"))
      (node (ref "R137") (pin "2") (pinfunction "2_2") (pintype "passive"))
      (node (ref "R173") (pin "2") (pinfunction "2_2") (pintype "passive"))
    )
    (net (code "70") (name "Net-(Q19-D)") (class "Default")
      (node (ref "Q19") (pin "3") (pinfunction "D_3") (pintype "passive"))
      (node (ref "R116") (pin "1") (pinfunction "1_1") (pintype "passive"))
    )
    (net (code "71") (name "Net-(Q20-D)") (class "Default")
      (node (ref "Q20") (pin "3") (pinfunction "D_3") (pintype "passive"))
      (node (ref "R142") (pin "1") (pinfunction "1_1") (pintype "passive"))
    )
    (net (code "72") (name "Net-(Q20-G)") (class "Default")
      (node (ref "Q20") (pin "1") (pinfunction "G_1") (pintype "passive"))
      (node (ref "R143") (pin "2") (pinfunction "2_2") (pintype "passive"))
      (node (ref "R176") (pin "2") (pinfunction "2_2") (pintype "passive"))
    )
    (net (code "73") (name "Net-(Q21-B)") (class "Default")
      (node (ref "C129") (pin "2") (pinfunction "2_2") (pintype "passive"))
      (node (ref "Q21") (pin "1") (pinfunction "B_1") (pintype "passive"))
      (node (ref "R191") (pin "1") (pinfunction "1_1") (pintype "passive"))
      (node (ref "U18") (pin "3") (pinfunction "K_3") (pintype "passive"))
    )
    (net (code "74") (name "Net-(Q21-E)") (class "Default")
      (node (ref "C132") (pin "2") (pinfunction "2_2") (pintype "passive"))
      (node (ref "FB11") (pin "2") (pinfunction "2_2") (pintype "passive"))
      (node (ref "Q21") (pin "2") (pinfunction "E_2") (pintype "passive"))
      (node (ref "R192") (pin "2") (pinfunction "2_2") (pintype "passive"))
    )
    (net (code "75") (name "Net-(R45-Pad1)") (class "Default")
      (node (ref "R45") (pin "1") (pinfunction "1_1") (pintype "passive"))
      (node (ref "R46") (pin "2") (pinfunction "2_2") (pintype "passive"))
    )
    (net (code "76") (name "Net-(R46-Pad1)") (class "Default")
      (node (ref "R46") (pin "1") (pinfunction "1_1") (pintype "passive"))
      (node (ref "R47") (pin "2") (pinfunction "2_2") (pintype "passive"))
    )
    (net (code "77") (name "Net-(R52-Pad1)") (class "Default")
      (node (ref "R52") (pin "1") (pinfunction "1_1") (pintype "passive"))
      (node (ref "R56") (pin "2") (pinfunction "2_2") (pintype "passive"))
    )
    (net (code "78") (name "Net-(R56-Pad1)") (class "Default")
      (node (ref "R56") (pin "1") (pinfunction "1_1") (pintype "passive"))
      (node (ref "R80") (pin "2") (pinfunction "2_2") (pintype "passive"))
    )
    (net (code "79") (name "Net-(R90-Pad1)") (class "Default")
      (node (ref "R90") (pin "1") (pinfunction "1_1") (pintype "passive"))
      (node (ref "R91") (pin "2") (pinfunction "2_2") (pintype "passive"))
    )
    (net (code "80") (name "Net-(R91-Pad1)") (class "Default")
      (node (ref "R91") (pin "1") (pinfunction "1_1") (pintype "passive"))
      (node (ref "R92") (pin "2") (pinfunction "2_2") (pintype "passive"))
    )
    (net (code "81") (name "Net-(R94-Pad1)") (class "Default")
      (node (ref "R94") (pin "1") (pinfunction "1_1") (pintype "passive"))
      (node (ref "R96") (pin "2") (pinfunction "2_2") (pintype "passive"))
    )
    (net (code "82") (name "Net-(R96-Pad1)") (class "Default")
      (node (ref "R96") (pin "1") (pinfunction "1_1") (pintype "passive"))
      (node (ref "R97") (pin "2") (pinfunction "2_2") (pintype "passive"))
    )
    (net (code "83") (name "Net-(U14-REF)") (class "Default")
      (node (ref "C107") (pin "1") (pinfunction "1_1") (pintype "passive"))
      (node (ref "R136") (pin "1") (pinfunction "1_1") (pintype "passive"))
      (node (ref "R139") (pin "2") (pinfunction "2_2") (pintype "passive"))
      (node (ref "U14") (pin "4") (pinfunction "REF_4") (pintype "input"))
    )
    (net (code "84") (name "Net-(U15A-A)") (class "Default")
      (node (ref "C122") (pin "2") (pinfunction "2_2") (pintype "passive"))
      (node (ref "R174") (pin "2") (pinfunction "2_2") (pintype "passive"))
      (node (ref "U15") (pin "1") (pinfunction "A_1") (pintype "input"))
    )
    (net (code "85") (name "Net-(U15A-B)") (class "Default")
      (node (ref "C121") (pin "2") (pinfunction "2_2") (pintype "passive"))
      (node (ref "R175") (pin "2") (pinfunction "2_2") (pintype "passive"))
      (node (ref "U15") (pin "2") (pinfunction "B_2") (pintype "input"))
    )
    (net (code "86") (name "Net-(U15A-Y)") (class "Default")
      (node (ref "R140") (pin "1") (pinfunction "1_1") (pintype "passive"))
      (node (ref "U15") (pin "4") (pinfunction "Y_4") (pintype "output"))
    )
    (net (code "87") (name "Net-(U16-IN+)") (class "Default")
      (node (ref "R140") (pin "2") (pinfunction "2_2") (pintype "passive"))
      (node (ref "U16") (pin "3") (pinfunction "IN+_3") (pintype "passive"))
    )
    (net (code "88") (name "Net-(U16-IN-)") (class "Default")
      (node (ref "R141") (pin "2") (pinfunction "2_2") (pintype "passive"))
      (node (ref "U16") (pin "1") (pinfunction "IN-_1") (pintype "passive"))
    )
    (net (code "89") (name "Net-(U16-OUT_SNK)") (class "Default")
      (node (ref "R18") (pin "1") (pinfunction "1_1") (pintype "passive"))
      (node (ref "U16") (pin "6") (pinfunction "OUT_SNK_6") (pintype "passive"))
    )
    (net (code "90") (name "Net-(U16-OUT_SRC)") (class "Default")
      (node (ref "R16") (pin "1") (pinfunction "1_1") (pintype "passive"))
      (node (ref "U16") (pin "5") (pinfunction "OUT_SRC_5") (pintype "passive"))
    )
    (net (code "91") (name "Net-(U16-VDD)") (class "Default")
      (node (ref "C112") (pin "2") (pinfunction "2_2") (pintype "passive"))
      (node (ref "FB14") (pin "1") (pinfunction "1_1") (pintype "passive"))
      (node (ref "U16") (pin "4") (pinfunction "VDD_4") (pintype "passive"))
    )
    (net (code "92") (name "Net-(U17-OUT)") (class "Default")
      (node (ref "C125") (pin "2") (pinfunction "2_2") (pintype "passive"))
      (node (ref "R189") (pin "2") (pinfunction "2_2") (pintype "passive"))
      (node (ref "R216") (pin "1") (pinfunction "1_1") (pintype "passive"))
      (node (ref "U17") (pin "4") (pinfunction "OUT_4") (pintype "output"))
    )
    (net (code "93") (name "Net-(U18-REF)") (class "Default")
      (node (ref "C129") (pin "1") (pinfunction "1_1") (pintype "passive"))
      (node (ref "R192") (pin "1") (pinfunction "1_1") (pintype "passive"))
      (node (ref "R193") (pin "2") (pinfunction "2_2") (pintype "passive"))
      (node (ref "U18") (pin "4") (pinfunction "REF_4") (pintype "input"))
    )
    (net (code "94") (name "Net-(U19A-VOUTA)") (class "Default")
      (node (ref "C52") (pin "2") (pinfunction "2_2") (pintype "passive"))
      (node (ref "R102") (pin "1") (pinfunction "1_1") (pintype "passive"))
      (node (ref "R110") (pin "1") (pinfunction "1_1") (pintype "passive"))
      (node (ref "U19") (pin "1") (pinfunction "VOUTA_1") (pintype "output"))
    )
    (net (code "95") (name "Net-(U19B-VOUTB)") (class "Default")
      (node (ref "C147") (pin "2") (pinfunction "2_2") (pintype "passive"))
      (node (ref "R101") (pin "1") (pinfunction "1_1") (pintype "passive"))
      (node (ref "R194") (pin "1") (pinfunction "1_1") (pintype "passive"))
      (node (ref "U19") (pin "7") (pinfunction "VOUTB_7") (pintype "output"))
    )
    (net (code "96") (name "Net-(U20-PA5)") (class "Default")
      (node (ref "R201") (pin "1") (pinfunction "1_1") (pintype "passive"))
      (node (ref "R207") (pin "1") (pinfunction "1_1") (pintype "passive"))
      (node (ref "U20") (pin "13") (pinfunction "PA5_13") (pintype "passive"))
    )
    (net (code "97") (name "Net-(U20-PB8-BOOT0)") (class "Default")
      (node (ref "R190") (pin "2") (pinfunction "2_2") (pintype "passive"))
      (node (ref "U20") (pin "46") (pinfunction "PB8-BOOT0_46") (pintype "passive"))
    )
    (net (code "98") (name "Net-(U21-VIN+)") (class "Default")
      (node (ref "C154") (pin "2") (pinfunction "2_2") (pintype "passive"))
      (node (ref "R206") (pin "1") (pinfunction "1_1") (pintype "passive"))
      (node (ref "U21") (pin "3") (pinfunction "VIN+_3") (pintype "input"))
    )
    (net (code "99") (name "Net-(U21-VIN-)") (class "Default")
      (node (ref "C152") (pin "1") (pinfunction "1_1") (pintype "passive"))
      (node (ref "R202") (pin "2") (pinfunction "2_2") (pintype "passive"))
      (node (ref "R203") (pin "1") (pinfunction "1_1") (pintype "passive"))
      (node (ref "U21") (pin "4") (pinfunction "VIN-_4") (pintype "input"))
    )
    (net (code "100") (name "Net-(U21-VOUT)") (class "Default")
      (node (ref "C152") (pin "2") (pinfunction "2_2") (pintype "passive"))
      (node (ref "R205") (pin "2") (pinfunction "2_2") (pintype "passive"))
      (node (ref "U21") (pin "1") (pinfunction "VOUT_1") (pintype "output"))
    )
    (net (code "101") (name "Net-(U22-K)") (class "Default")
      (node (ref "R204") (pin "1") (pinfunction "1_1") (pintype "passive"))
      (node (ref "R206") (pin "2") (pinfunction "2_2") (pintype "passive"))
      (node (ref "U22") (pin "3") (pinfunction "K_3") (pintype "passive"))
      (node (ref "U22") (pin "4") (pinfunction "REF_4") (pintype "input"))
    )
    (net (code "102") (name "TOP_LF_GND") (class "Default")
      (node (ref "C102") (pin "1") (pinfunction "1_1") (pintype "passive"))
      (node (ref "C103") (pin "2") (pinfunction "2_2") (pintype "passive"))
      (node (ref "C104") (pin "2") (pinfunction "2_2") (pintype "passive"))
      (node (ref "C105") (pin "2") (pinfunction "2_2") (pintype "passive"))
      (node (ref "C106") (pin "1") (pinfunction "1_1") (pintype "passive"))
      (node (ref "C109") (pin "1") (pinfunction "1_1") (pintype "passive"))
      (node (ref "C110") (pin "1") (pinfunction "1_1") (pintype "passive"))
      (node (ref "C111") (pin "1") (pinfunction "1_1") (pintype "passive"))
      (node (ref "C121") (pin "1") (pinfunction "1_1") (pintype "passive"))
      (node (ref "C122") (pin "1") (pinfunction "1_1") (pintype "passive"))
      (node (ref "C126") (pin "1") (pinfunction "1_1") (pintype "passive"))
      (node (ref "C127") (pin "1") (pinfunction "1_1") (pintype "passive"))
      (node (ref "C128") (pin "2") (pinfunction "2_2") (pintype "passive"))
      (node (ref "C130") (pin "1") (pinfunction "1_1") (pintype "passive"))
      (node (ref "C132") (pin "1") (pinfunction "1_1") (pintype "passive"))
      (node (ref "C141") (pin "1") (pinfunction "1_1") (pintype "passive"))
      (node (ref "C143") (pin "1") (pinfunction "1_1") (pintype "passive"))
      (node (ref "C144") (pin "2") (pinfunction "2_2") (pintype "passive"))
      (node (ref "C148") (pin "1") (pinfunction "1_1") (pintype "passive"))
      (node (ref "C150") (pin "1") (pinfunction "1_1") (pintype "passive"))
      (node (ref "C151") (pin "1") (pinfunction "1_1") (pintype "passive"))
      (node (ref "C153") (pin "1") (pinfunction "1_1") (pintype "passive"))
      (node (ref "C154") (pin "1") (pinfunction "1_1") (pintype "passive"))
      (node (ref "C155") (pin "1") (pinfunction "1_1") (pintype "passive"))
      (node (ref "C156") (pin "1") (pinfunction "1_1") (pintype "passive"))
      (node (ref "C158") (pin "1") (pinfunction "1_1") (pintype "passive"))
      (node (ref "C161") (pin "2") (pinfunction "2_2") (pintype "passive"))
      (node (ref "C162") (pin "2") (pinfunction "2_2") (pintype "passive"))
      (node (ref "C163") (pin "1") (pinfunction "1_1") (pintype "passive"))
      (node (ref "C30") (pin "1") (pinfunction "1_1") (pintype "passive"))
      (node (ref "C41") (pin "1") (pinfunction "1_1") (pintype "passive"))
      (node (ref "C60") (pin "2") (pinfunction "2_2") (pintype "passive"))
      (node (ref "C65") (pin "1") (pinfunction "1_1") (pintype "passive"))
      (node (ref "C66") (pin "2") (pinfunction "2_2") (pintype "passive"))
      (node (ref "C67") (pin "1") (pinfunction "1_1") (pintype "passive"))
      (node (ref "C72") (pin "1") (pinfunction "1_1") (pintype "passive"))
      (node (ref "C93") (pin "1") (pinfunction "1_1") (pintype "passive"))
      (node (ref "C94") (pin "1") (pinfunction "1_1") (pintype "passive"))
      (node (ref "C95") (pin "1") (pinfunction "1_1") (pintype "passive"))
      (node (ref "C97") (pin "1") (pinfunction "1_1") (pintype "passive"))
      (node (ref "C99") (pin "1") (pinfunction "1_1") (pintype "passive"))
      (node (ref "D11") (pin "2") (pinfunction "A_2") (pintype "passive"))
      (node (ref "D12") (pin "2") (pinfunction "A_2") (pintype "passive"))
      (node (ref "D22") (pin "2") (pinfunction "K_2") (pintype "passive"))
      (node (ref "IC6") (pin "4") (pinfunction "AGND_4") (pintype "passive"))
      (node (ref "IC6") (pin "5") (pinfunction "NC_5") (pintype "passive"))
      (node (ref "IC6") (pin "8") (pinfunction "PGND_8") (pintype "passive"))
      (node (ref "IC6") (pin "9") (pinfunction "EP_9") (pintype "passive"))
      (node (ref "J3") (pin "3") (pinfunction "3_3") (pintype "passive"))
      (node (ref "J3") (pin "6") (pinfunction "6_6") (pintype "passive"))
      (node (ref "NTC4") (pin "1") (pinfunction "1_1") (pintype "passive"))
      (node (ref "P4") (pin "3") (pinfunction "3_3") (pintype "passive"))
      (node (ref "Q14") (pin "1") (pinfunction "E_1") (pintype "passive"))
      (node (ref "Q15") (pin "2") (pinfunction "S_2") (pintype "passive"))
      (node (ref "Q19") (pin "2") (pinfunction "S_2") (pintype "passive"))
      (node (ref "Q20") (pin "2") (pinfunction "S_2") (pintype "passive"))
      (node (ref "R119") (pin "1") (pinfunction "1_1") (pintype "passive"))
      (node (ref "R130") (pin "1") (pinfunction "1_1") (pintype "passive"))
      (node (ref "R131") (pin "1") (pinfunction "1_1") (pintype "passive"))
      (node (ref "R139") (pin "1") (pinfunction "1_1") (pintype "passive"))
      (node (ref "R141") (pin "1") (pinfunction "1_1") (pintype "passive"))
      (node (ref "R172") (pin "1") (pinfunction "1_1") (pintype "passive"))
      (node (ref "R173") (pin "1") (pinfunction "1_1") (pintype "passive"))
      (node (ref "R176") (pin "1") (pinfunction "1_1") (pintype "passive"))
      (node (ref "R179") (pin "1") (pinfunction "1_1") (pintype "passive"))
      (node (ref "R180") (pin "2") (pinfunction "2_2") (pintype "passive"))
      (node (ref "R190") (pin "1") (pinfunction "1_1") (pintype "passive"))
      (node (ref "R193") (pin "1") (pinfunction "1_1") (pintype "passive"))
      (node (ref "R203") (pin "2") (pinfunction "2_2") (pintype "passive"))
      (node (ref "R209") (pin "1") (pinfunction "1_1") (pintype "passive"))
      (node (ref "U14") (pin "5") (pinfunction "A_5") (pintype "passive"))
      (node (ref "U15") (pin "3") (pinfunction "GND_3") (pintype "power_in"))
      (node (ref "U17") (pin "2") (pinfunction "V-_2") (pintype "power_in"))
      (node (ref "U18") (pin "5") (pinfunction "A_5") (pintype "passive"))
      (node (ref "U19") (pin "4") (pinfunction "VSS_4") (pintype "power_in"))
      (node (ref "U20") (pin "49") (pinfunction "VSS_49") (pintype "passive"))
      (node (ref "U21") (pin "2") (pinfunction "VSS_2") (pintype "power_in"))
      (node (ref "U22") (pin "5") (pinfunction "A_5") (pintype "passive"))
    )
    (net (code "103") (name "TOP_LF_VREF") (class "Default")
      (node (ref "C153") (pin "2") (pinfunction "2_2") (pintype "passive"))
      (node (ref "R202") (pin "1") (pinfunction "1_1") (pintype "passive"))
      (node (ref "R205") (pin "1") (pinfunction "1_1") (pintype "passive"))
      (node (ref "U20") (pin "20") (pinfunction "VREF+_20") (pintype "passive"))
    )
    (net (code "104") (name "TOP_LF_V_3V3A") (class "Default")
      (node (ref "C130") (pin "2") (pinfunction "2_2") (pintype "passive"))
      (node (ref "C155") (pin "2") (pinfunction "2_2") (pintype "passive"))
      (node (ref "C30") (pin "2") (pinfunction "2_2") (pintype "passive"))
      (node (ref "C41") (pin "2") (pinfunction "2_2") (pintype "passive"))
      (node (ref "FB11") (pin "1") (pinfunction "1_1") (pintype "passive"))
      (node (ref "R186") (pin "2") (pinfunction "2_2") (pintype "passive"))
      (node (ref "R204") (pin "2") (pinfunction "2_2") (pintype "passive"))
      (node (ref "U17") (pin "5") (pinfunction "V+_5") (pintype "power_in"))
      (node (ref "U19") (pin "8") (pinfunction "VDD_8") (pintype "power_in"))
      (node (ref "U20") (pin "21") (pinfunction "VDDA_21") (pintype "passive"))
      (node (ref "U21") (pin "5") (pinfunction "VDD_5") (pintype "power_in"))
    )
    (net (code "105") (name "TOP_LF_V_3V3D") (class "Default")
      (node (ref "C109") (pin "2") (pinfunction "2_2") (pintype "passive"))
      (node (ref "C128") (pin "1") (pinfunction "1_1") (pintype "passive"))
      (node (ref "C141") (pin "2") (pinfunction "2_2") (pintype "passive"))
      (node (ref "C161") (pin "1") (pinfunction "1_1") (pintype "passive"))
      (node (ref "C162") (pin "1") (pinfunction "1_1") (pintype "passive"))
      (node (ref "C66") (pin "1") (pinfunction "1_1") (pintype "passive"))
      (node (ref "C67") (pin "2") (pinfunction "2_2") (pintype "passive"))
      (node (ref "C99") (pin "2") (pinfunction "2_2") (pintype "passive"))
      (node (ref "FB12") (pin "1") (pinfunction "1_1") (pintype "passive"))
      (node (ref "J3") (pin "1") (pinfunction "1_1") (pintype "passive"))
      (node (ref "LED3") (pin "2") (pinfunction "A_2") (pintype "passive"))
      (node (ref "P4") (pin "1") (pinfunction "1_1") (pintype "passive"))
      (node (ref "U15") (pin "5") (pinfunction "VCC_5") (pintype "power_in"))
      (node (ref "U20") (pin "1") (pinfunction "VBAT_1") (pintype "passive"))
      (node (ref "U20") (pin "23") (pinfunction "VDD_1_23") (pintype "passive"))
      (node (ref "U20") (pin "35") (pinfunction "VDD_2_35") (pintype "passive"))
      (node (ref "U20") (pin "48") (pinfunction "VDD_3_48") (pintype "passive"))
    )
    (net (code "106") (name "TOP_LF_V_3VN") (class "Default")
      (node (ref "C103") (pin "1") (pinfunction "1_1") (pintype "passive"))
      (node (ref "C104") (pin "1") (pinfunction "1_1") (pintype "passive"))
      (node (ref "C105") (pin "1") (pinfunction "1_1") (pintype "passive"))
      (node (ref "C111") (pin "2") (pinfunction "2_2") (pintype "passive"))
      (node (ref "C112") (pin "1") (pinfunction "1_1") (pintype "passive"))
      (node (ref "D22") (pin "1") (pinfunction "A_1") (pintype "passive"))
      (node (ref "R115") (pin "2") (pinfunction "2_2") (pintype "passive"))
      (node (ref "U16") (pin "2") (pinfunction "GND_2") (pintype "passive"))
    )
    (net (code "107") (name "TOP_LF_V_5VP") (class "Default")
      (node (ref "C143") (pin "2") (pinfunction "2_2") (pintype "passive"))
      (node (ref "C158") (pin "2") (pinfunction "2_2") (pintype "passive"))
      (node (ref "C96") (pin "2") (pinfunction "2_2") (pintype "passive"))
      (node (ref "C97") (pin "2") (pinfunction "2_2") (pintype "passive"))
      (node (ref "FB10") (pin "2") (pinfunction "2_2") (pintype "passive"))
      (node (ref "FB8") (pin "2") (pinfunction "2_2") (pintype "passive"))
      (node (ref "IC6") (pin "2") (pinfunction "VIN_2") (pintype "passive"))
      (node (ref "L5") (pin "1") (pinfunction "1_1") (pintype "passive"))
      (node (ref "Q13") (pin "3") (pinfunction "C_3") (pintype "passive"))
      (node (ref "Q21") (pin "3") (pinfunction "C_3") (pintype "passive"))
      (node (ref "R133") (pin "2") (pinfunction "2_2") (pintype "passive"))
      (node (ref "R178") (pin "2") (pinfunction "2_2") (pintype "passive"))
      (node (ref "R191") (pin "2") (pinfunction "2_2") (pintype "passive"))
    )
    (net (code "108") (name "TOP_LF_V_16VP") (class "Default")
      (node (ref "C160") (pin "2") (pinfunction "2_2") (pintype "passive"))
      (node (ref "C93") (pin "2") (pinfunction "2_2") (pintype "passive"))
      (node (ref "C94") (pin "2") (pinfunction "2_2") (pintype "passive"))
      (node (ref "C95") (pin "2") (pinfunction "2_2") (pintype "passive"))
      (node (ref "FB14") (pin "2") (pinfunction "2_2") (pintype "passive"))
      (node (ref "FB19") (pin "2") (pinfunction "2_2") (pintype "passive"))
      (node (ref "R177") (pin "1") (pinfunction "1_1") (pintype "passive"))
    )
    (net (code "109") (name "unconnected-(CONN_VAC-Pad1)") (class "Default")
      (node (ref "CONN_VAC") (pin "1") (pinfunction "1_1") (pintype "passive"))
    )
    (net (code "110") (name "unconnected-(CONN_VAC-Pad2)") (class "Default")
      (node (ref "CONN_VAC") (pin "2") (pinfunction "2_2") (pintype "passive"))
    )
    (net (code "111") (name "unconnected-(CONN_VAC-Pad3)") (class "Default")
      (node (ref "CONN_VAC") (pin "3") (pinfunction "3_3") (pintype "passive"))
    )
    (net (code "112") (name "unconnected-(CONN_VAC-Pad4)") (class "Default")
      (node (ref "CONN_VAC") (pin "4") (pinfunction "4_4") (pintype "passive"))
    )
    (net (code "113") (name "unconnected-(CONN_VAC-Pad5)") (class "Default")
      (node (ref "CONN_VAC") (pin "5") (pinfunction "5_5") (pintype "passive"))
    )
    (net (code "114") (name "unconnected-(CONN_VAC-Pad6)") (class "Default")
      (node (ref "CONN_VAC") (pin "6") (pinfunction "6_6") (pintype "passive"))
    )
    (net (code "115") (name "unconnected-(CONN_VAC-Pad7)") (class "Default")
      (node (ref "CONN_VAC") (pin "7") (pinfunction "7_7") (pintype "passive"))
    )
    (net (code "116") (name "unconnected-(CONN_VAC-Pad8)") (class "Default")
      (node (ref "CONN_VAC") (pin "8") (pinfunction "8_8") (pintype "passive"))
    )
    (net (code "117") (name "unconnected-(CONN_VAC-Pad9)") (class "Default")
      (node (ref "CONN_VAC") (pin "9") (pinfunction "9_9") (pintype "passive"))
    )
    (net (code "118") (name "unconnected-(CONN_VAC-Pad10)") (class "Default")
      (node (ref "CONN_VAC") (pin "10") (pinfunction "10_10") (pintype "passive"))
    )
    (net (code "119") (name "unconnected-(CONN_VAC-Pad11)") (class "Default")
      (node (ref "CONN_VAC") (pin "11") (pinfunction "11_11") (pintype "passive"))
    )
    (net (code "120") (name "unconnected-(CONN_VAC-Pad12)") (class "Default")
      (node (ref "CONN_VAC") (pin "12") (pinfunction "12_12") (pintype "passive"))
    )
    (net (code "121") (name "unconnected-(CONN_VAC-Pad13)") (class "Default")
      (node (ref "CONN_VAC") (pin "13") (pinfunction "13_13") (pintype "passive"))
    )
    (net (code "122") (name "unconnected-(CONN_VAC-Pad14)") (class "Default")
      (node (ref "CONN_VAC") (pin "14") (pinfunction "14_14") (pintype "passive"))
    )
    (net (code "123") (name "unconnected-(CONN_VAC-Pad15)") (class "Default")
      (node (ref "CONN_VAC") (pin "15") (pinfunction "15_15") (pintype "passive"))
    )
    (net (code "124") (name "unconnected-(CONN_VAC-Pad16)") (class "Default")
      (node (ref "CONN_VAC") (pin "16") (pinfunction "16_16") (pintype "passive"))
    )
    (net (code "125") (name "unconnected-(P4-Pad6)") (class "Default")
      (node (ref "P4") (pin "6") (pinfunction "6_6") (pintype "passive"))
    )
    (net (code "126") (name "unconnected-(U14-NC-Pad1)") (class "Default")
      (node (ref "U14") (pin "1") (pinfunction "NC_1") (pintype "passive"))
    )
    (net (code "127") (name "unconnected-(U14-NC-Pad2)") (class "Default")
      (node (ref "U14") (pin "2") (pinfunction "NC_2") (pintype "passive"))
    )
    (net (code "128") (name "unconnected-(U18-NC-Pad1)") (class "Default")
      (node (ref "U18") (pin "1") (pinfunction "NC_1") (pintype "passive"))
    )
    (net (code "129") (name "unconnected-(U18-NC-Pad2)") (class "Default")
      (node (ref "U18") (pin "2") (pinfunction "NC_2") (pintype "passive"))
    )
    (net (code "130") (name "unconnected-(U19B-VDD-Pad8)") (class "Default")
      (node (ref "U19") (pin "8") (pinfunction "VDD_8") (pintype "power_in"))
    )
    (net (code "131") (name "unconnected-(U19B-VSS-Pad4)") (class "Default")
      (node (ref "U19") (pin "4") (pinfunction "VSS_4") (pintype "power_in"))
    )
    (net (code "132") (name "unconnected-(U20-PA12-Pad34)") (class "Default")
      (node (ref "U20") (pin "34") (pinfunction "PA12_34") (pintype "passive"))
    )
    (net (code "133") (name "unconnected-(U20-PA15-Pad38)") (class "Default")
      (node (ref "U20") (pin "38") (pinfunction "PA15_38") (pintype "passive"))
    )
    (net (code "134") (name "unconnected-(U20-PB6-Pad44)") (class "Default")
      (node (ref "U20") (pin "44") (pinfunction "PB6_44") (pintype "passive"))
    )
    (net (code "135") (name "unconnected-(U20-PB9-Pad47)") (class "Default")
      (node (ref "U20") (pin "47") (pinfunction "PB9_47") (pintype "passive"))
    )
    (net (code "136") (name "unconnected-(U20-PB10-Pad22)") (class "Default")
      (node (ref "U20") (pin "22") (pinfunction "PB10_22") (pintype "passive"))
    )
    (net (code "137") (name "unconnected-(U20-PC6-Pad29)") (class "Default")
      (node (ref "U20") (pin "29") (pinfunction "PC6_29") (pintype "passive"))
    )
    (net (code "138") (name "unconnected-(U20-PC10-Pad39)") (class "Default")
      (node (ref "U20") (pin "39") (pinfunction "PC10_39") (pintype "passive"))
    )
    (net (code "139") (name "unconnected-(U20-PC11-Pad40)") (class "Default")
      (node (ref "U20") (pin "40") (pinfunction "PC11_40") (pintype "passive"))
    )
    (net (code "140") (name "unconnected-(U20-PC14-OSC32_IN-Pad3)") (class "Default")
      (node (ref "U20") (pin "3") (pinfunction "PC14-OSC32_IN_3") (pintype "passive"))
    )
    (net (code "141") (name "unconnected-(U20-PC15-OSC32_OUT-Pad4)") (class "Default")
      (node (ref "U20") (pin "4") (pinfunction "PC15-OSC32_OUT_4") (pintype "passive"))
    )
    (net (code "142") (name "unconnected-(U22-NC-Pad1)") (class "Default")
      (node (ref "U22") (pin "1") (pinfunction "NC_1") (pintype "passive"))
    )
    (net (code "143") (name "unconnected-(U22-NC-Pad2)") (class "Default")
      (node (ref "U22") (pin "2") (pinfunction "NC_2") (pintype "passive"))
    )
  )
)
